# e-ink-display-v120.net
KiCad netlist of a schematic drawn in EAGLE
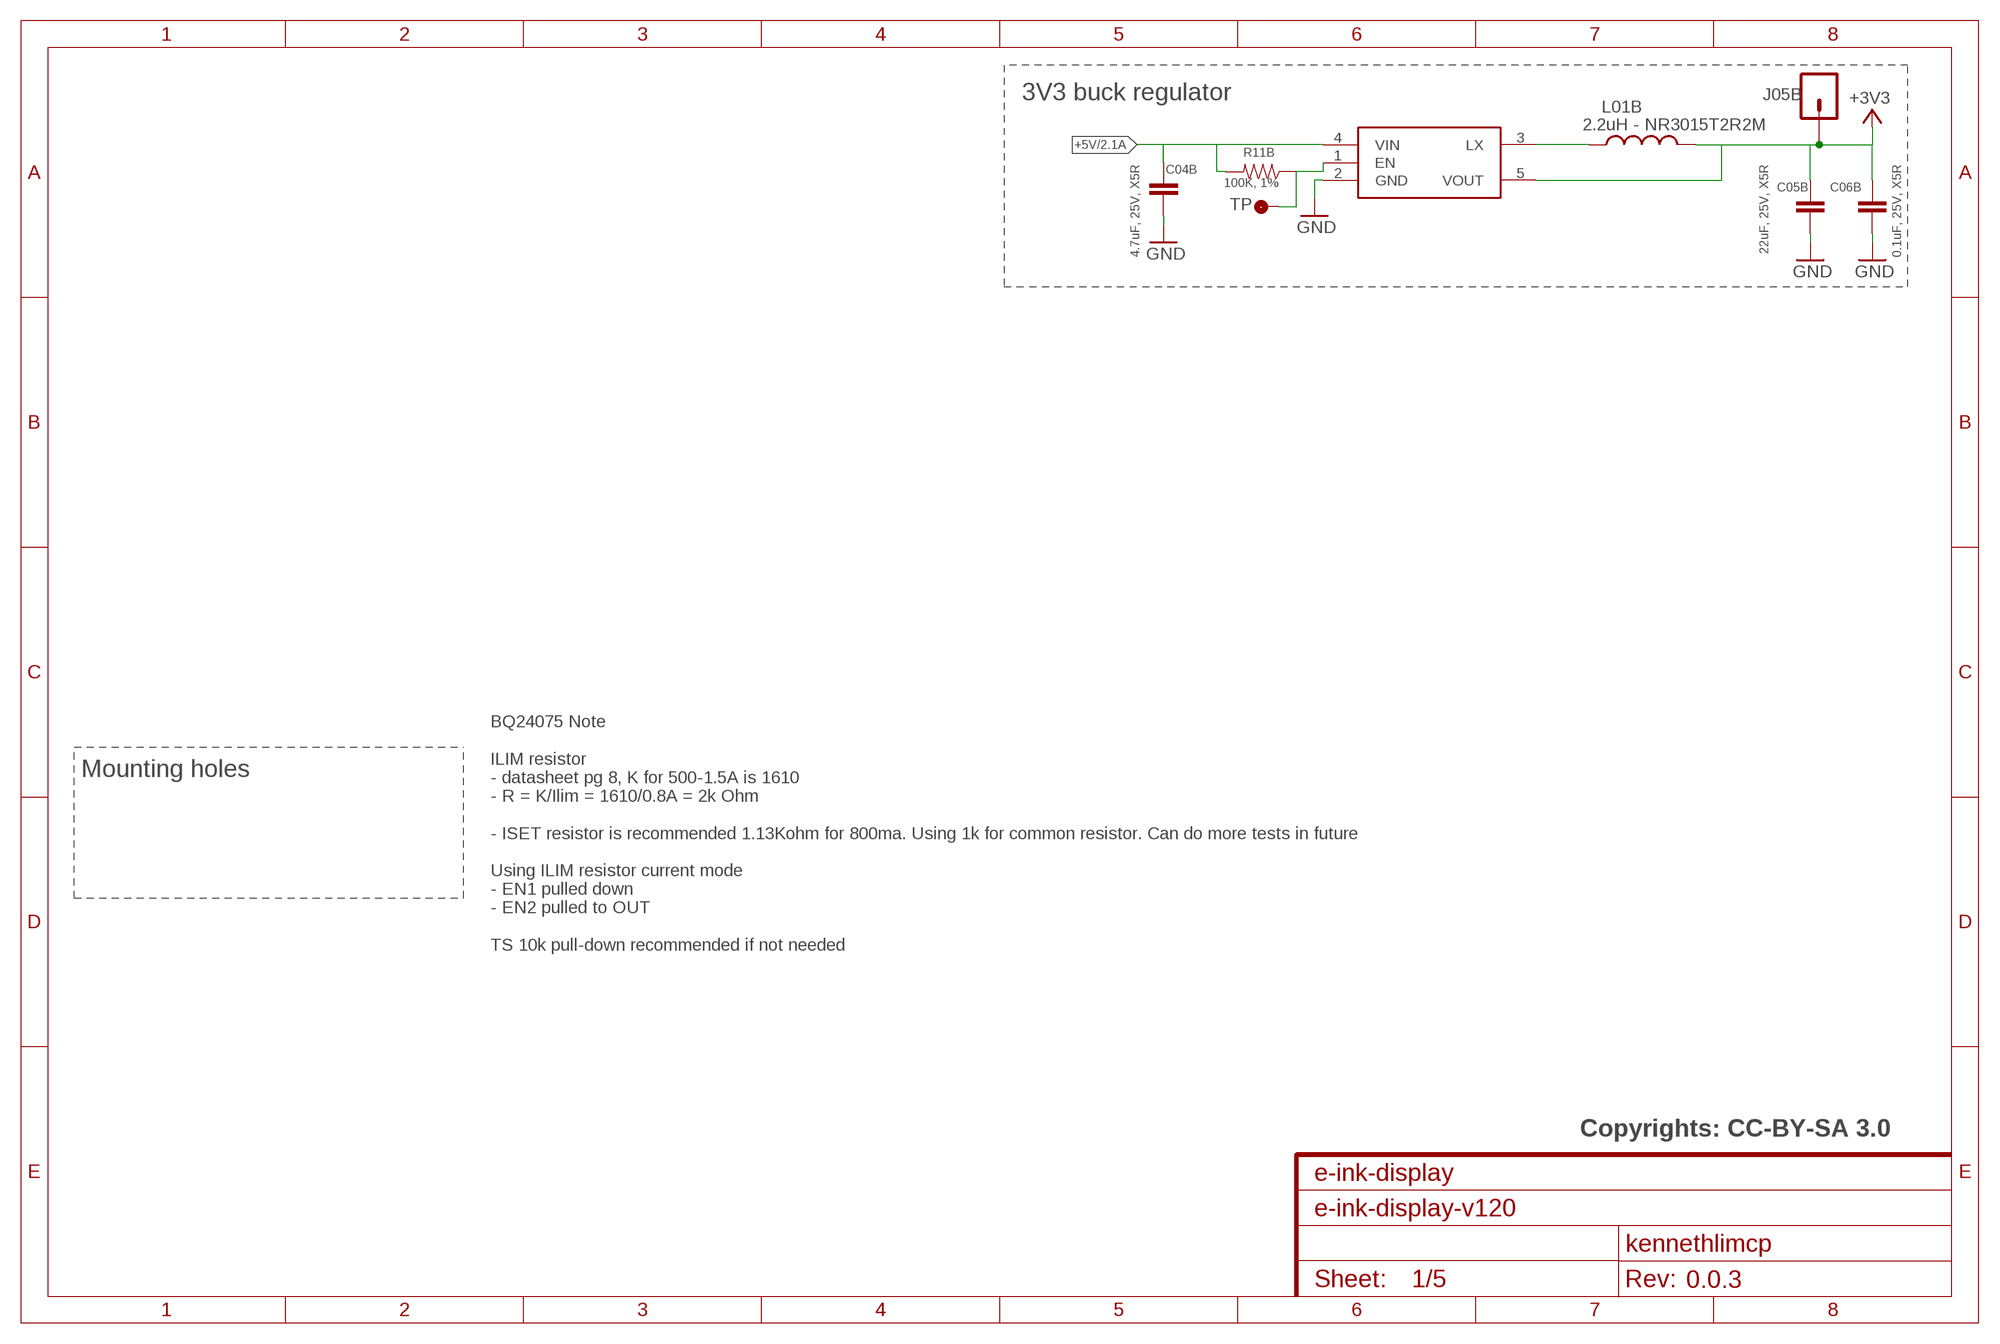
[diagram p0: schematic, sheet 1]
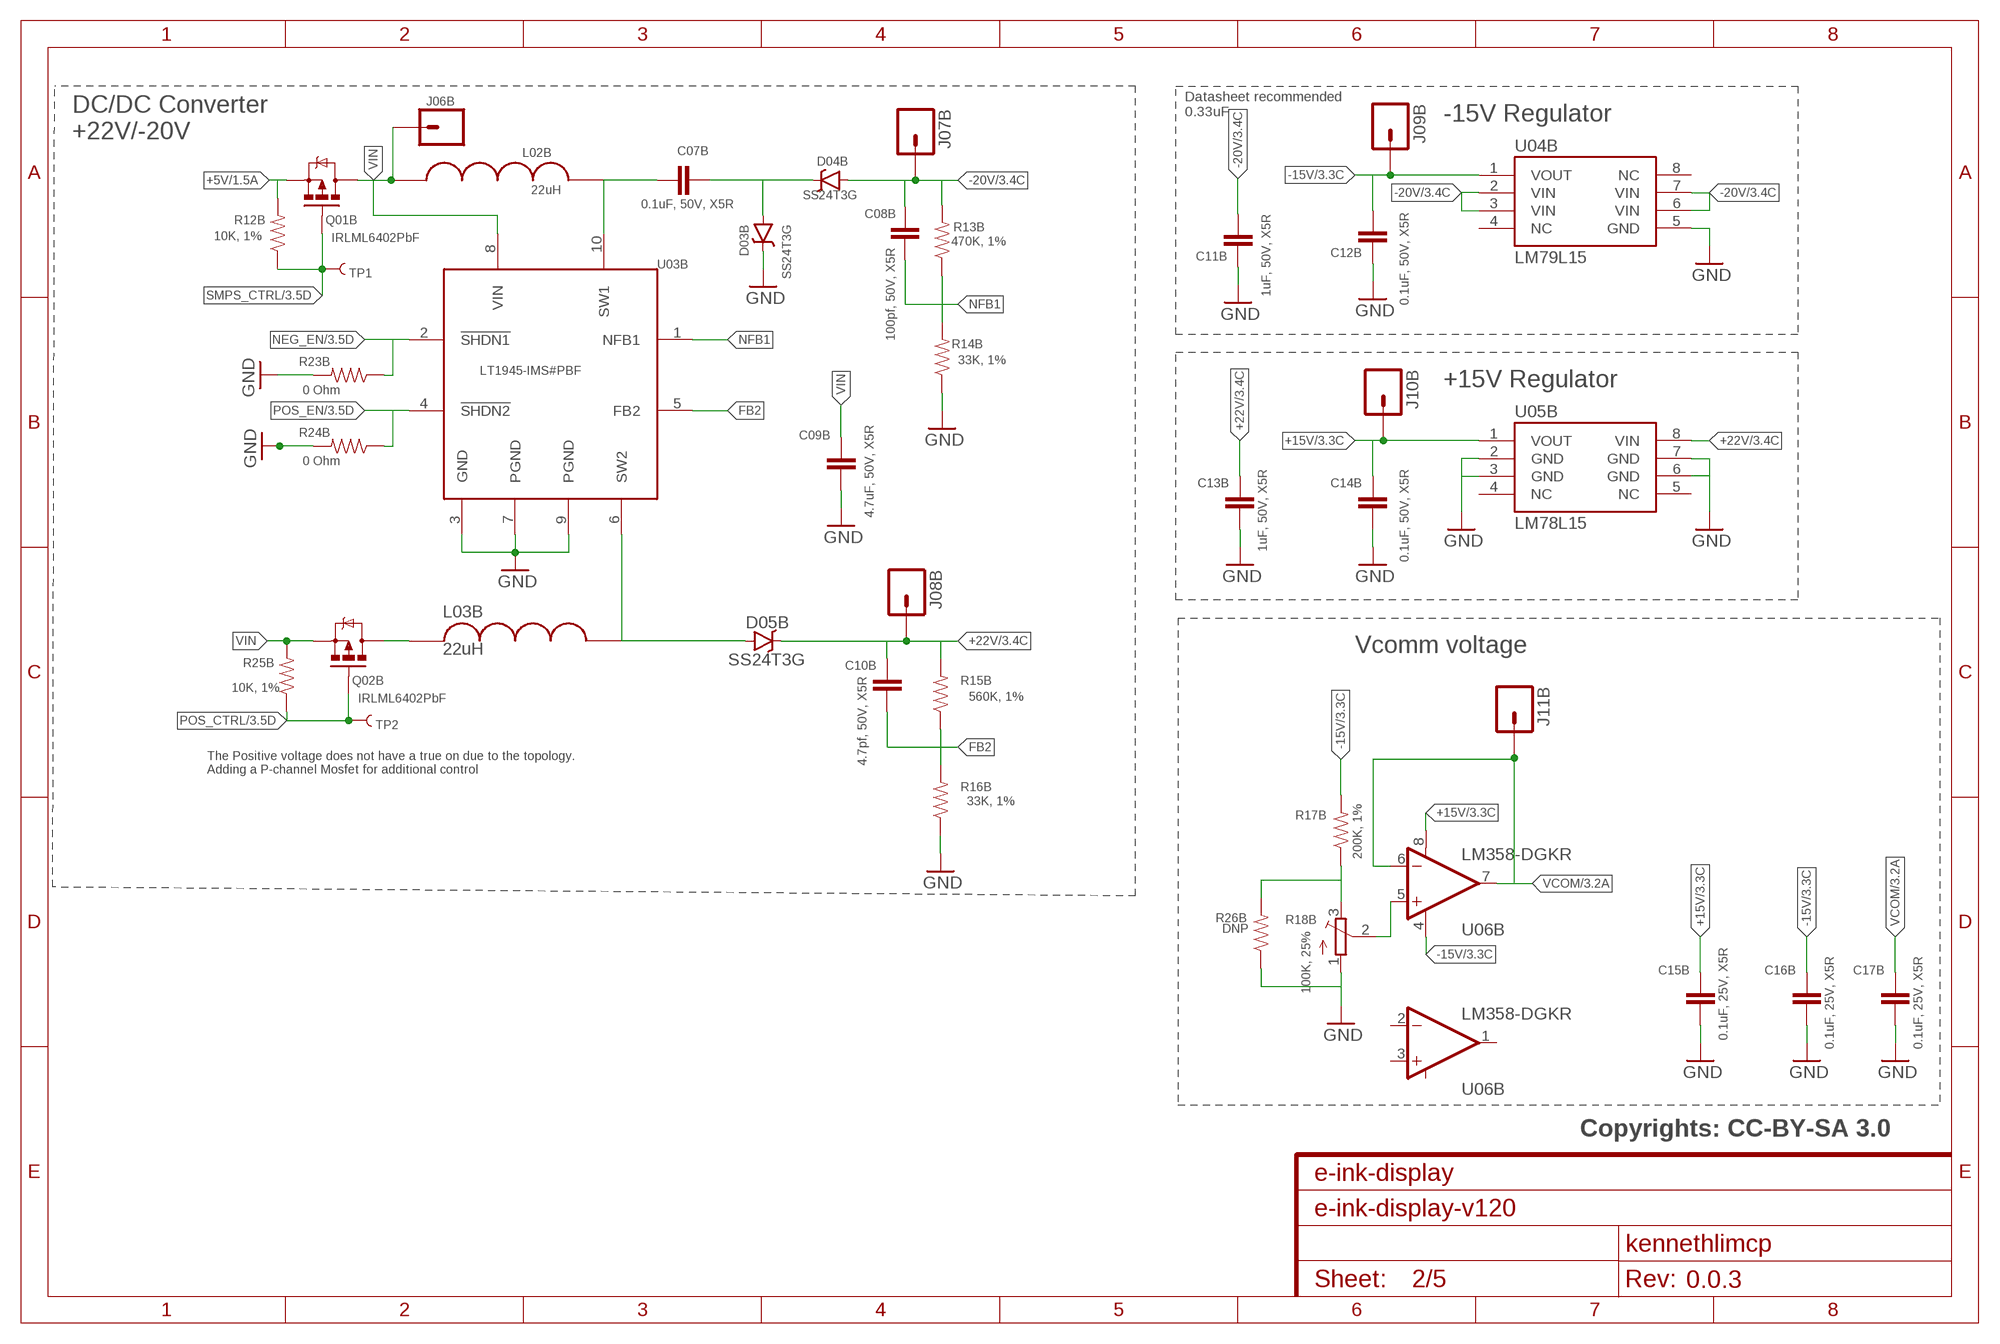
[diagram p1: schematic, sheet 2]
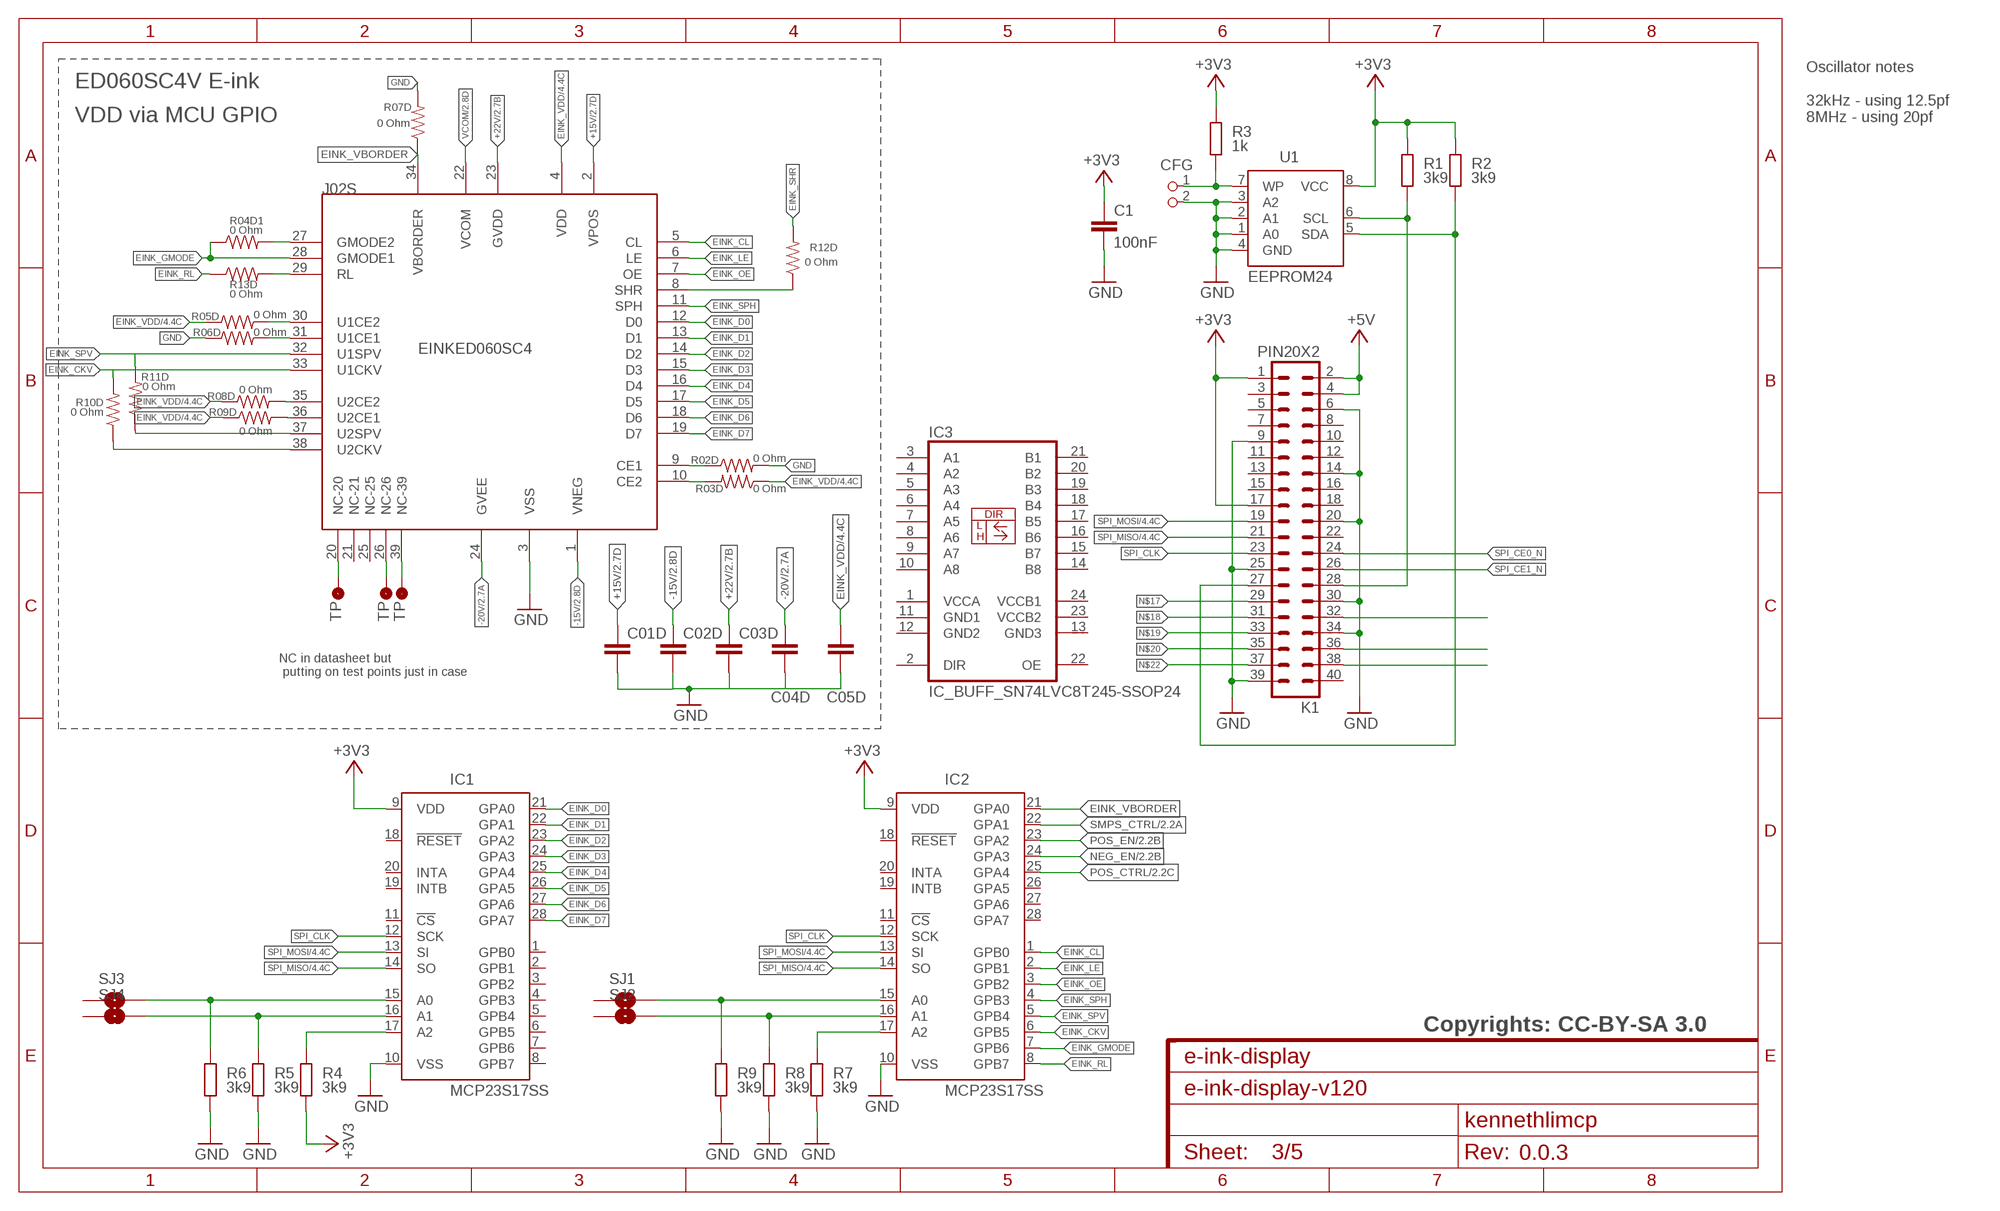
[diagram p2: schematic, sheet 3]
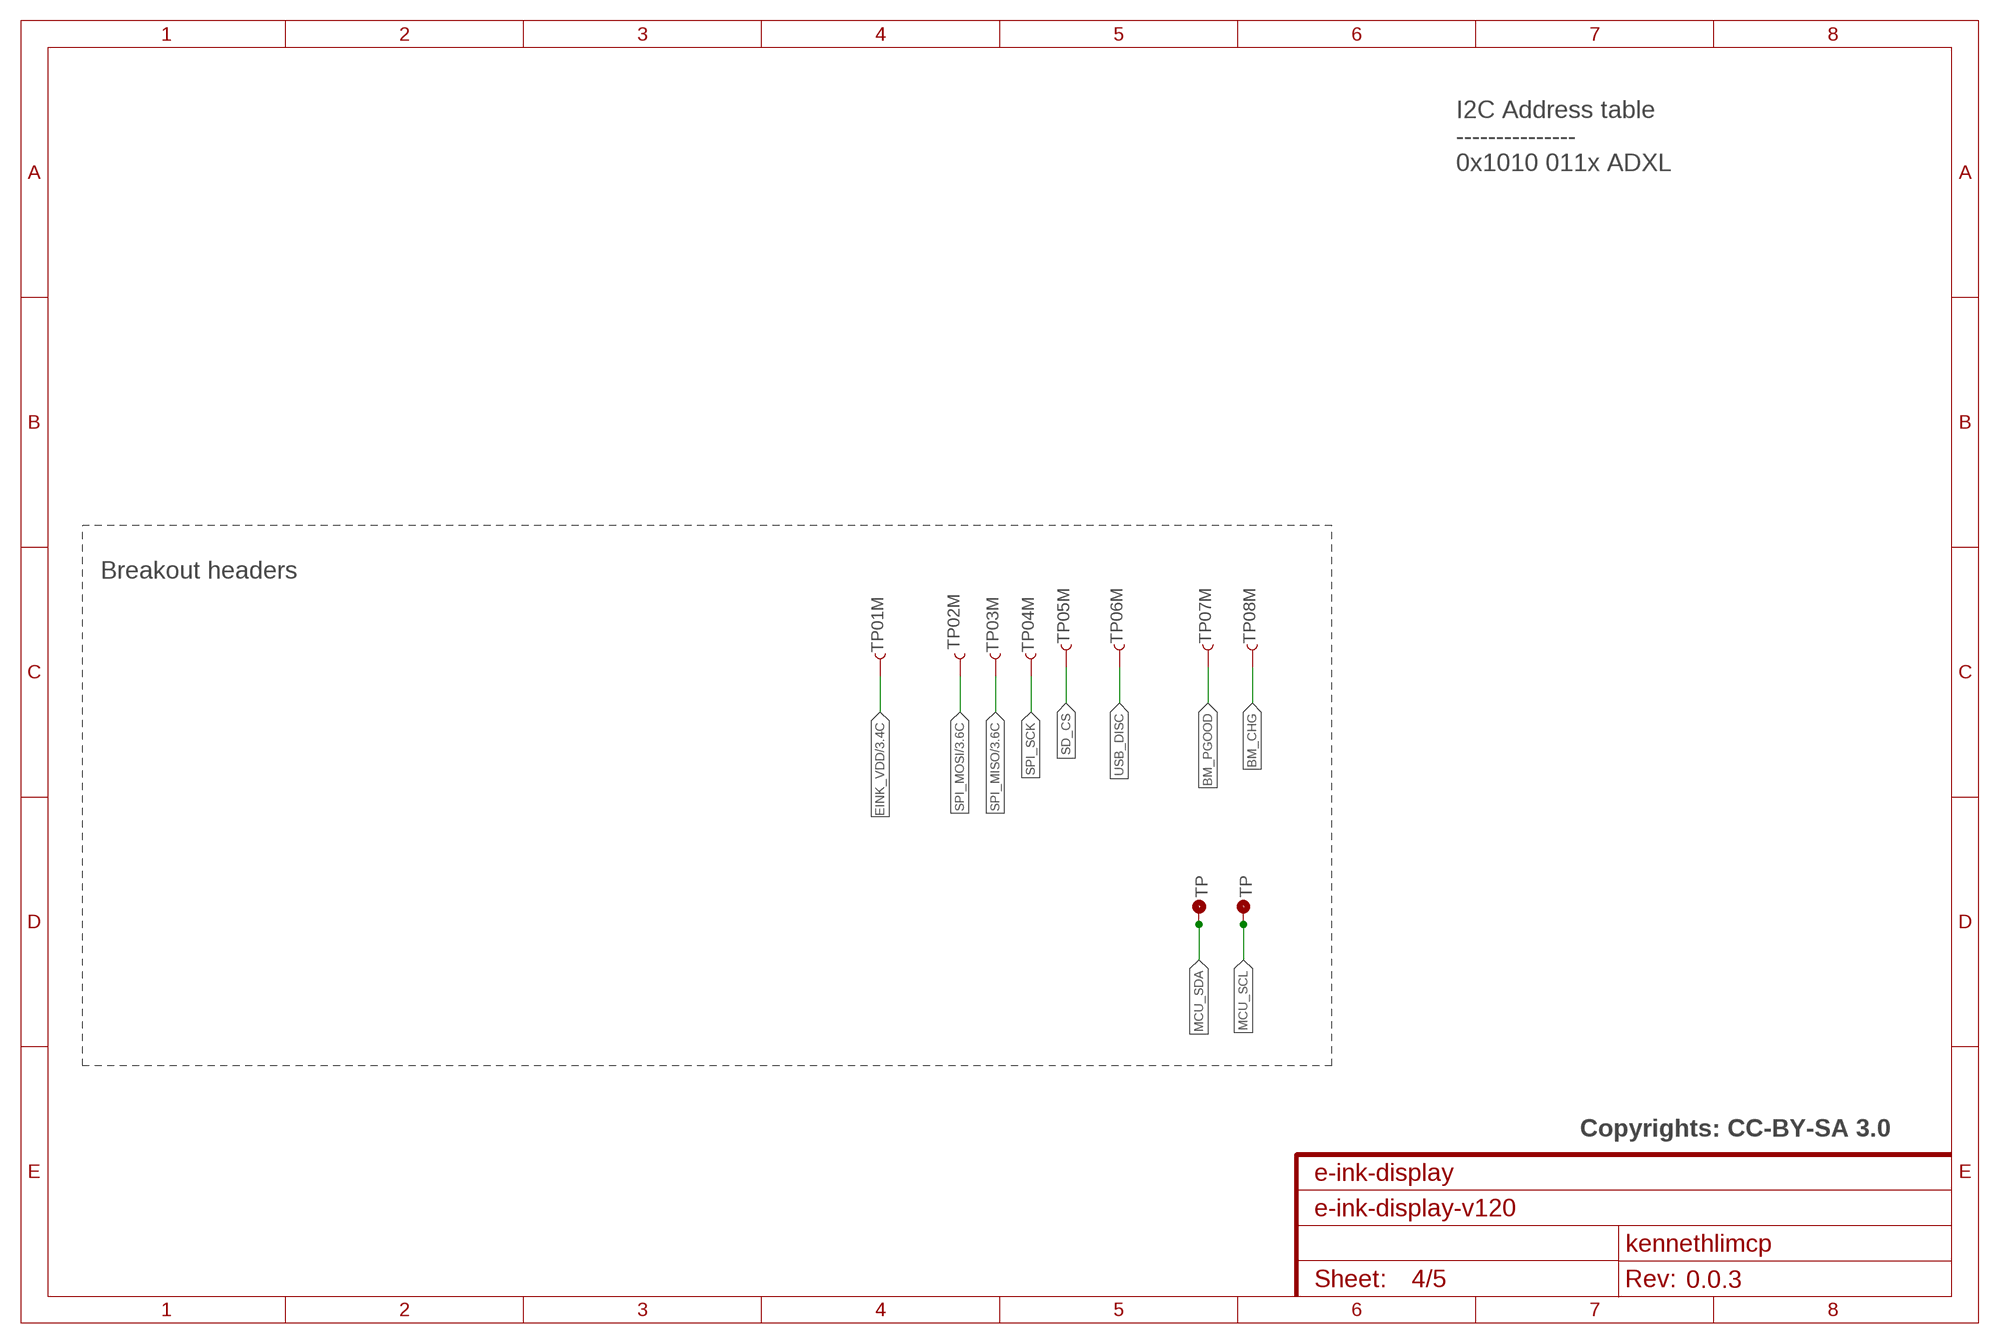
[diagram p3: schematic, sheet 4]
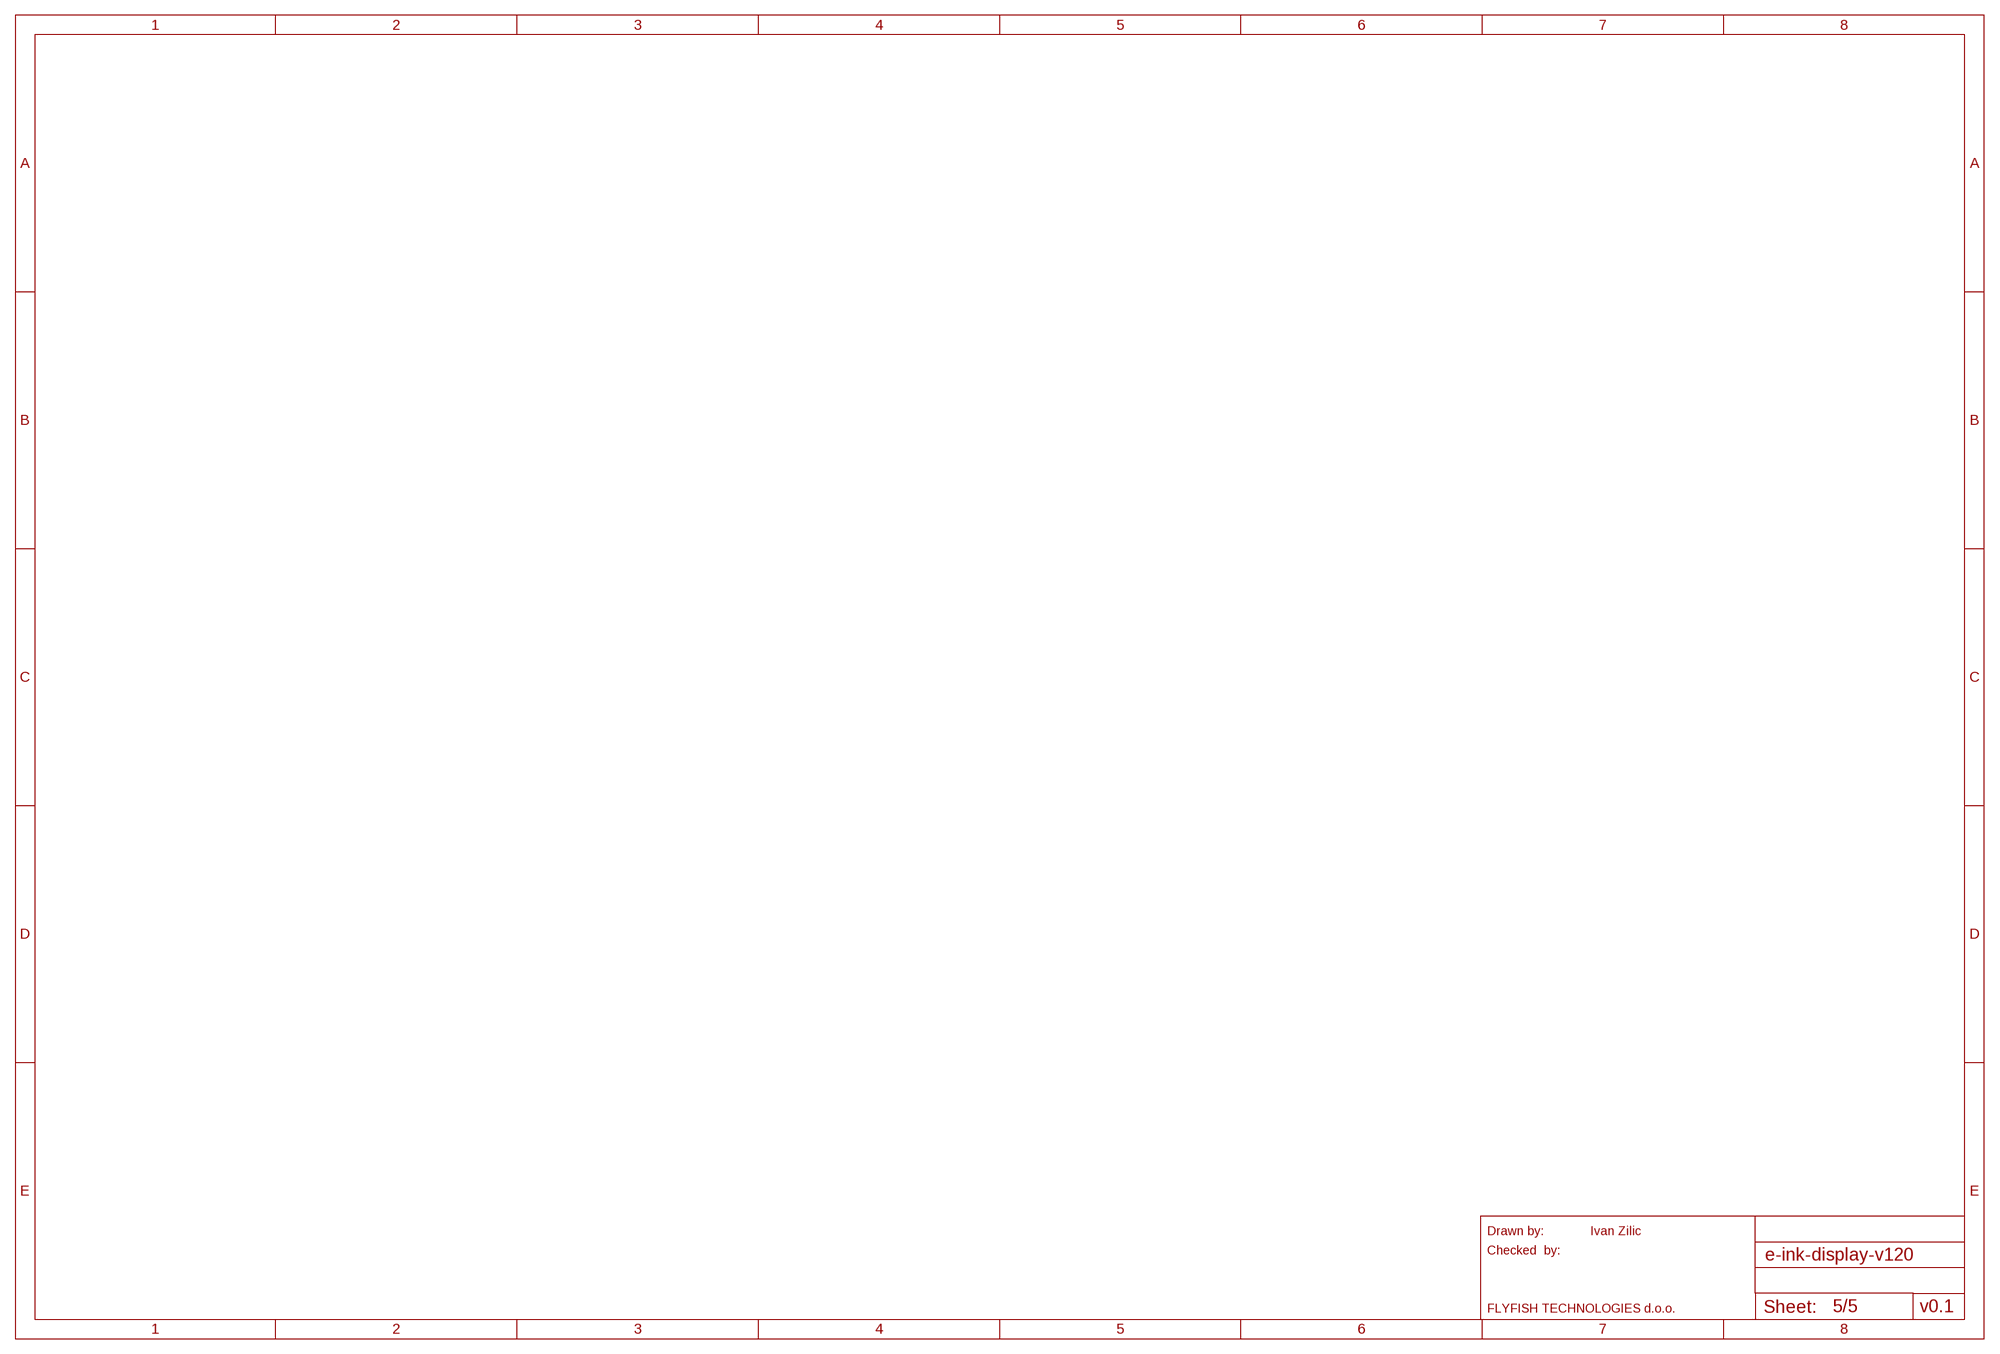
[diagram p4: schematic, sheet 5]

(export (version "E")
  (design (tool "Eeschema 10.0.6"))
  (components
    (comp (ref "TP01M")
      (value "TEST-POINTRD_THRU")
      (footprint "eagle-import:TP-RD_15TH")
      (libsource (lib "eagle-import") (part "TEST-POINTRD_THRU"))
    )
    (comp (ref "TP02M")
      (value "TEST-POINTRD_THRU")
      (footprint "eagle-import:TP-RD_15TH")
      (libsource (lib "eagle-import") (part "TEST-POINTRD_THRU"))
    )
    (comp (ref "TP03M")
      (value "TEST-POINTTP_15TH_THRU")
      (footprint "eagle-import:TP_15TH")
      (libsource (lib "eagle-import") (part "TEST-POINTTP_15TH_THRU"))
    )
    (comp (ref "TP04M")
      (value "TEST-POINTRD_THRU")
      (footprint "eagle-import:TP-RD_15TH")
      (libsource (lib "eagle-import") (part "TEST-POINTRD_THRU"))
    )
    (comp (ref "TP05M")
      (value "TEST-POINTRD_THRU")
      (footprint "eagle-import:TP-RD_15TH")
      (libsource (lib "eagle-import") (part "TEST-POINTRD_THRU"))
    )
    (comp (ref "TP06M")
      (value "TEST-POINTRD_THRU")
      (footprint "eagle-import:TP-RD_15TH")
      (libsource (lib "eagle-import") (part "TEST-POINTRD_THRU"))
    )
    (comp (ref "TP07M")
      (value "TEST-POINTRD_THRU")
      (footprint "eagle-import:TP-RD_15TH")
      (libsource (lib "eagle-import") (part "TEST-POINTRD_THRU"))
    )
    (comp (ref "TP08M")
      (value "TEST-POINTRD_THRU")
      (footprint "eagle-import:TP-RD_15TH")
      (libsource (lib "eagle-import") (part "TEST-POINTRD_THRU"))
    )
    (comp (ref "TP17M")
      (value "TP1")
      (footprint "eagle-import:TP35_BOT")
      (libsource (lib "eagle-import") (part "TP1"))
    )
    (comp (ref "TP18M")
      (value "TP1")
      (footprint "eagle-import:TP35_BOT")
      (libsource (lib "eagle-import") (part "TP1"))
    )
    (comp (ref "C04B")
      (value "4.7uF, 25V, X5R")
      (footprint "eagle-import:0603-CAP")
      (libsource (lib "eagle-import") (part "CAP0603-CAP"))
    )
    (comp (ref "C05B")
      (value "22uF, 25V, X5R")
      (footprint "eagle-import:0603-CAP")
      (libsource (lib "eagle-import") (part "CAP0603-CAP"))
    )
    (comp (ref "C06B")
      (value "0.1uF, 25V, X5R")
      (footprint "eagle-import:0603-CAP")
      (libsource (lib "eagle-import") (part "CAP0603-CAP"))
    )
    (comp (ref "J05B")
      (value "M01PTH")
      (footprint "eagle-import:1X01")
      (libsource (lib "eagle-import") (part "M01PTH"))
    )
    (comp (ref "L01B")
      (value "2.2uH - NR3015T2R2M")
      (footprint "eagle-import:INDUCTOR-NR3015")
      (libsource (lib "eagle-import") (part "INDUCTOR-SPARKFUNNR3015T4R7M"))
    )
    (comp (ref "R11B")
      (value "100K, 1%")
      (footprint "eagle-import:0603-RES")
      (libsource (lib "eagle-import") (part "RESISTOR0603-RES"))
    )
    (comp (ref "TP01B")
      (value "TP1")
      (footprint "eagle-import:TP35_BOT")
      (libsource (lib "eagle-import") (part "TP1"))
    )
    (comp (ref "U02B")
      (value "R8008-33")
      (footprint "eagle-import:SOT23-5")
      (libsource (lib "eagle-import") (part "R8008-33"))
    )
    (comp (ref "C1")
      (value "100nF")
      (footprint "eagle-import:C0805K")
      (libsource (lib "eagle-import") (part "C-EUC0805K"))
    )
    (comp (ref "C01D")
      (value "100nF")
      (footprint "eagle-import:0603-CAP")
      (libsource (lib "eagle-import") (part "CAP0603-CAP"))
    )
    (comp (ref "C02D")
      (value "100nF")
      (footprint "eagle-import:0603-CAP")
      (libsource (lib "eagle-import") (part "CAP0603-CAP"))
    )
    (comp (ref "C03D")
      (value "100nF")
      (footprint "eagle-import:0603-CAP")
      (libsource (lib "eagle-import") (part "CAP0603-CAP"))
    )
    (comp (ref "C04D")
      (value "100nF")
      (footprint "eagle-import:0603-CAP")
      (libsource (lib "eagle-import") (part "CAP0603-CAP"))
    )
    (comp (ref "C05D")
      (value "100nF")
      (footprint "eagle-import:0603-CAP")
      (libsource (lib "eagle-import") (part "CAP0603-CAP"))
    )
    (comp (ref "CFG")
      (value "PIN2_100")
      (footprint "eagle-import:PIN_W_2")
      (libsource (lib "eagle-import") (part "PIN2_100"))
    )
    (comp (ref "IC1")
      (value "MCP23S17SS")
      (footprint "eagle-import:SSOP28")
      (fields (field (name "MF") "MICROCHIP") (field (name "MPN") "MCP23S17-E/SS"))
      (libsource (lib "eagle-import") (part "MCP23S17SS"))
    )
    (comp (ref "IC2")
      (value "MCP23S17SS")
      (footprint "eagle-import:SSOP28")
      (fields (field (name "MF") "MICROCHIP") (field (name "MPN") "MCP23S17-E/SS"))
      (libsource (lib "eagle-import") (part "MCP23S17SS"))
    )
    (comp (ref "IC3")
      (value "IC_BUFF_SN74LVC8T245-SSOP24")
      (footprint "eagle-import:SSOP24")
      (libsource (lib "eagle-import") (part "IC_BUFF_SN74LVC8T245-SSOP24"))
    )
    (comp (ref "J02S")
      (value "EINKED060SC4")
      (footprint "eagle-import:FPC-0.3-39")
      (libsource (lib "eagle-import") (part "EINKED060SC4"))
    )
    (comp (ref "K1")
      (value "PIN20X2")
      (footprint "eagle-import:PIN_20X2")
      (libsource (lib "eagle-import") (part "PIN20X2"))
    )
    (comp (ref "R1")
      (value "3k9")
      (footprint "eagle-import:M0805")
      (fields (field (name "TOLERANCE") "5%"))
      (libsource (lib "eagle-import") (part "R-EU_M0805"))
    )
    (comp (ref "R2")
      (value "3k9")
      (footprint "eagle-import:M0805")
      (fields (field (name "TOLERANCE") "5%"))
      (libsource (lib "eagle-import") (part "R-EU_M0805"))
    )
    (comp (ref "R02D")
      (value "0 Ohm")
      (footprint "eagle-import:0603-RES")
      (libsource (lib "eagle-import") (part "RESISTOR0603-RES"))
    )
    (comp (ref "R3")
      (value "1k")
      (footprint "eagle-import:M0805")
      (fields (field (name "TOLERANCE") "5%"))
      (libsource (lib "eagle-import") (part "R-EU_M0805"))
    )
    (comp (ref "R03D")
      (value "0 Ohm")
      (footprint "eagle-import:0603-RES")
      (libsource (lib "eagle-import") (part "RESISTOR0603-RES"))
    )
    (comp (ref "R4")
      (value "3k9")
      (footprint "eagle-import:M0805")
      (fields (field (name "TOLERANCE") "5%"))
      (libsource (lib "eagle-import") (part "R-EU_M0805"))
    )
    (comp (ref "R04D1")
      (value "0 Ohm")
      (footprint "eagle-import:0603-RES")
      (libsource (lib "eagle-import") (part "RESISTOR0603-RES"))
    )
    (comp (ref "R5")
      (value "3k9")
      (footprint "eagle-import:M0805")
      (fields (field (name "TOLERANCE") "5%"))
      (libsource (lib "eagle-import") (part "R-EU_M0805"))
    )
    (comp (ref "R05D")
      (value "0 Ohm")
      (footprint "eagle-import:0603-RES")
      (libsource (lib "eagle-import") (part "RESISTOR0603-RES"))
    )
    (comp (ref "R6")
      (value "3k9")
      (footprint "eagle-import:M0805")
      (fields (field (name "TOLERANCE") "5%"))
      (libsource (lib "eagle-import") (part "R-EU_M0805"))
    )
    (comp (ref "R06D")
      (value "0 Ohm")
      (footprint "eagle-import:0603-RES")
      (libsource (lib "eagle-import") (part "RESISTOR0603-RES"))
    )
    (comp (ref "R7")
      (value "3k9")
      (footprint "eagle-import:M0805")
      (fields (field (name "TOLERANCE") "5%"))
      (libsource (lib "eagle-import") (part "R-EU_M0805"))
    )
    (comp (ref "R07D")
      (value "0 Ohm")
      (footprint "eagle-import:0603-RES")
      (libsource (lib "eagle-import") (part "RESISTOR0603-RES"))
    )
    (comp (ref "R8")
      (value "3k9")
      (footprint "eagle-import:M0805")
      (fields (field (name "TOLERANCE") "5%"))
      (libsource (lib "eagle-import") (part "R-EU_M0805"))
    )
    (comp (ref "R08D")
      (value "0 Ohm")
      (footprint "eagle-import:0603-RES")
      (libsource (lib "eagle-import") (part "RESISTOR0603-RES"))
    )
    (comp (ref "R9")
      (value "3k9")
      (footprint "eagle-import:M0805")
      (fields (field (name "TOLERANCE") "5%"))
      (libsource (lib "eagle-import") (part "R-EU_M0805"))
    )
    (comp (ref "R09D")
      (value "0 Ohm")
      (footprint "eagle-import:0603-RES")
      (libsource (lib "eagle-import") (part "RESISTOR0603-RES"))
    )
    (comp (ref "R10D")
      (value "0 Ohm")
      (footprint "eagle-import:0603-RES")
      (libsource (lib "eagle-import") (part "RESISTOR0603-RES"))
    )
    (comp (ref "R11D")
      (value "0 Ohm")
      (footprint "eagle-import:0603-RES")
      (libsource (lib "eagle-import") (part "RESISTOR0603-RES"))
    )
    (comp (ref "R12D")
      (value "0 Ohm")
      (footprint "eagle-import:0603-RES")
      (libsource (lib "eagle-import") (part "RESISTOR0603-RES"))
    )
    (comp (ref "R13D")
      (value "0 Ohm")
      (footprint "eagle-import:0603-RES")
      (libsource (lib "eagle-import") (part "RESISTOR0603-RES"))
    )
    (comp (ref "SJ1")
      (value "SOLDERJUMPERNO")
      (footprint "eagle-import:SJ_2S-NO")
      (libsource (lib "eagle-import") (part "SOLDERJUMPERNO"))
    )
    (comp (ref "SJ2")
      (value "SOLDERJUMPERNO")
      (footprint "eagle-import:SJ_2S-NO")
      (libsource (lib "eagle-import") (part "SOLDERJUMPERNO"))
    )
    (comp (ref "SJ3")
      (value "SOLDERJUMPERNO")
      (footprint "eagle-import:SJ_2S-NO")
      (libsource (lib "eagle-import") (part "SOLDERJUMPERNO"))
    )
    (comp (ref "SJ4")
      (value "SOLDERJUMPERNO")
      (footprint "eagle-import:SJ_2S-NO")
      (libsource (lib "eagle-import") (part "SOLDERJUMPERNO"))
    )
    (comp (ref "U$1")
      (value "TP1")
      (footprint "eagle-import:TP35_BOT")
      (libsource (lib "eagle-import") (part "TP1"))
    )
    (comp (ref "U$8")
      (value "TP1")
      (footprint "eagle-import:TP35_BOT")
      (libsource (lib "eagle-import") (part "TP1"))
    )
    (comp (ref "U$9")
      (value "TP1")
      (footprint "eagle-import:TP35_BOT")
      (libsource (lib "eagle-import") (part "TP1"))
    )
    (comp (ref "U1")
      (value "EEPROM24")
      (footprint "eagle-import:SOIC8")
      (libsource (lib "eagle-import") (part "EEPROM24"))
    )
    (comp (ref "C07B")
      (value "0.1uF, 50V, X5R")
      (footprint "eagle-import:0603-CAP")
      (libsource (lib "eagle-import") (part "CAP0603-CAP"))
    )
    (comp (ref "C08B")
      (value "100pf, 50V, X5R")
      (footprint "eagle-import:0603-CAP")
      (libsource (lib "eagle-import") (part "CAP0603-CAP"))
    )
    (comp (ref "C09B")
      (value "4.7uF, 50V, X5R")
      (footprint "eagle-import:0603-CAP")
      (libsource (lib "eagle-import") (part "CAP0603-CAP"))
    )
    (comp (ref "C10B")
      (value "4.7pf, 50V, X5R")
      (footprint "eagle-import:0603-CAP")
      (libsource (lib "eagle-import") (part "CAP0603-CAP"))
    )
    (comp (ref "C11B")
      (value "1uF, 50V, X5R")
      (footprint "eagle-import:0603-CAP")
      (libsource (lib "eagle-import") (part "CAP0603-CAP"))
    )
    (comp (ref "C12B")
      (value "0.1uF, 50V, X5R")
      (footprint "eagle-import:0603-CAP")
      (libsource (lib "eagle-import") (part "CAP0603-CAP"))
    )
    (comp (ref "C13B")
      (value "1uF, 50V, X5R")
      (footprint "eagle-import:0603-CAP")
      (libsource (lib "eagle-import") (part "CAP0603-CAP"))
    )
    (comp (ref "C14B")
      (value "0.1uF, 50V, X5R")
      (footprint "eagle-import:0603-CAP")
      (libsource (lib "eagle-import") (part "CAP0603-CAP"))
    )
    (comp (ref "C15B")
      (value "0.1uF, 25V, X5R")
      (footprint "eagle-import:0603-CAP")
      (libsource (lib "eagle-import") (part "CAP0603-CAP"))
    )
    (comp (ref "C16B")
      (value "0.1uF, 25V, X5R")
      (footprint "eagle-import:0603-CAP")
      (libsource (lib "eagle-import") (part "CAP0603-CAP"))
    )
    (comp (ref "C17B")
      (value "0.1uF, 25V, X5R")
      (footprint "eagle-import:0603-CAP")
      (libsource (lib "eagle-import") (part "CAP0603-CAP"))
    )
    (comp (ref "D03B")
      (value "SS24T3G")
      (footprint "eagle-import:SMA-DIODE")
      (libsource (lib "eagle-import") (part "DIODE-SCHOTTKY-SS24T3G"))
    )
    (comp (ref "D04B")
      (value "SS24T3G")
      (footprint "eagle-import:SMA-DIODE")
      (libsource (lib "eagle-import") (part "DIODE-SCHOTTKY-SS24T3G"))
    )
    (comp (ref "D05B")
      (value "SS24T3G")
      (footprint "eagle-import:SMA-DIODE")
      (libsource (lib "eagle-import") (part "DIODE-SCHOTTKY-SS24T3G"))
    )
    (comp (ref "J06B")
      (value "M01PTH")
      (footprint "eagle-import:1X01")
      (libsource (lib "eagle-import") (part "M01PTH"))
    )
    (comp (ref "J07B")
      (value "M01PTH")
      (footprint "eagle-import:1X01")
      (libsource (lib "eagle-import") (part "M01PTH"))
    )
    (comp (ref "J08B")
      (value "M01PTH")
      (footprint "eagle-import:1X01")
      (libsource (lib "eagle-import") (part "M01PTH"))
    )
    (comp (ref "J09B")
      (value "M01PTH")
      (footprint "eagle-import:1X01")
      (libsource (lib "eagle-import") (part "M01PTH"))
    )
    (comp (ref "J10B")
      (value "M01PTH")
      (footprint "eagle-import:1X01")
      (libsource (lib "eagle-import") (part "M01PTH"))
    )
    (comp (ref "J11B")
      (value "M01PTH")
      (footprint "eagle-import:1X01")
      (libsource (lib "eagle-import") (part "M01PTH"))
    )
    (comp (ref "L02B")
      (value "22uH")
      (footprint "eagle-import:4040(1515)")
      (libsource (lib "eagle-import") (part "03-INDUCTOR"))
    )
    (comp (ref "L03B")
      (value "22uH")
      (footprint "eagle-import:4040(1515)")
      (libsource (lib "eagle-import") (part "03-INDUCTOR"))
    )
    (comp (ref "Q01B")
      (value "IRLML6402PbF")
      (footprint "eagle-import:SOT23-3")
      (libsource (lib "eagle-import") (part "MOSFET-PCHANNELSMD"))
    )
    (comp (ref "Q02B")
      (value "IRLML6402PbF")
      (footprint "eagle-import:SOT23-3")
      (libsource (lib "eagle-import") (part "MOSFET-PCHANNELSMD"))
    )
    (comp (ref "R12B")
      (value "10K, 1%")
      (footprint "eagle-import:0603-RES")
      (libsource (lib "eagle-import") (part "RESISTOR0603-RES"))
    )
    (comp (ref "R13B")
      (value "470K, 1%")
      (footprint "eagle-import:0603-RES")
      (libsource (lib "eagle-import") (part "RESISTOR0603-RES"))
    )
    (comp (ref "R14B")
      (value "33K, 1%")
      (footprint "eagle-import:0603-RES")
      (libsource (lib "eagle-import") (part "RESISTOR0603-RES"))
    )
    (comp (ref "R15B")
      (value "560K, 1%")
      (footprint "eagle-import:0603-RES")
      (libsource (lib "eagle-import") (part "RESISTOR0603-RES"))
    )
    (comp (ref "R16B")
      (value "33K, 1%")
      (footprint "eagle-import:0603-RES")
      (libsource (lib "eagle-import") (part "RESISTOR0603-RES"))
    )
    (comp (ref "R17B")
      (value "200K, 1%")
      (footprint "eagle-import:0603-RES")
      (libsource (lib "eagle-import") (part "RESISTOR0603-RES"))
    )
    (comp (ref "R18B")
      (value "100K, 25%")
      (footprint "eagle-import:TC33X")
      (libsource (lib "eagle-import") (part "TRIMPOTTC33X"))
    )
    (comp (ref "R23B")
      (value "0 Ohm")
      (footprint "eagle-import:0603-RES")
      (libsource (lib "eagle-import") (part "RESISTOR0603-RES"))
    )
    (comp (ref "R24B")
      (value "0 Ohm")
      (footprint "eagle-import:0603-RES")
      (libsource (lib "eagle-import") (part "RESISTOR0603-RES"))
    )
    (comp (ref "R25B")
      (value "10K, 1%")
      (footprint "eagle-import:0603-RES")
      (libsource (lib "eagle-import") (part "RESISTOR0603-RES"))
    )
    (comp (ref "R26B")
      (value "DNP")
      (footprint "eagle-import:0603-RES")
      (libsource (lib "eagle-import") (part "RESISTOR0603-RES"))
    )
    (comp (ref "TP1")
      (value "TEST-POINTRD_THRU")
      (footprint "eagle-import:TP-RD_15TH")
      (libsource (lib "eagle-import") (part "TEST-POINTRD_THRU"))
    )
    (comp (ref "TP2")
      (value "TEST-POINTRD_THRU")
      (footprint "eagle-import:TP-RD_15TH")
      (libsource (lib "eagle-import") (part "TEST-POINTRD_THRU"))
    )
    (comp (ref "U03B")
      (value "LT1945-IMS#PBF")
      (footprint "eagle-import:MSOP-10")
      (libsource (lib "eagle-import") (part "LT1945-IMS#PBF"))
    )
    (comp (ref "U04B")
      (value "LM79L15")
      (footprint "eagle-import:SO08")
      (libsource (lib "eagle-import") (part "LM79L15"))
    )
    (comp (ref "U05B")
      (value "LM78L15")
      (footprint "eagle-import:SO08")
      (libsource (lib "eagle-import") (part "LM78L15"))
    )
    (comp (ref "U06B")
      (value "LM358-DGKR")
      (footprint "eagle-import:MSOP-8")
      (libsource (lib "eagle-import") (part "LM358-DGKR"))
    )
  )
  (nets
    (net (code "1") (name "+3V3") (class "Default")
      (node (ref "C05B") (pin "2") (pinfunction "2_2") (pintype "passive"))
      (node (ref "C06B") (pin "2") (pinfunction "2_2") (pintype "passive"))
      (node (ref "C1") (pin "1") (pinfunction "1_1") (pintype "passive"))
      (node (ref "IC1") (pin "9") (pinfunction "VDD_9") (pintype "power_in"))
      (node (ref "IC2") (pin "9") (pinfunction "VDD_9") (pintype "power_in"))
      (node (ref "J05B") (pin "1") (pinfunction "1_1") (pintype "passive"))
      (node (ref "K1") (pin "1") (pinfunction "1_1") (pintype "passive"))
      (node (ref "K1") (pin "17") (pinfunction "17_17") (pintype "passive"))
      (node (ref "L01B") (pin "2") (pinfunction "2_2") (pintype "passive"))
      (node (ref "R1") (pin "2") (pinfunction "2_2") (pintype "passive"))
      (node (ref "R2") (pin "2") (pinfunction "2_2") (pintype "passive"))
      (node (ref "R3") (pin "2") (pinfunction "2_2") (pintype "passive"))
      (node (ref "R4") (pin "1") (pinfunction "1_1") (pintype "passive"))
      (node (ref "U02B") (pin "5") (pinfunction "VOUT_5") (pintype "bidirectional"))
      (node (ref "U1") (pin "8") (pinfunction "VCC_8") (pintype "power_in"))
    )
    (net (code "2") (name "+5V") (class "Default")
      (node (ref "C04B") (pin "2") (pinfunction "2_2") (pintype "passive"))
      (node (ref "K1") (pin "2") (pinfunction "2_2") (pintype "passive"))
      (node (ref "K1") (pin "4") (pinfunction "4_4") (pintype "passive"))
      (node (ref "Q01B") (pin "2") (pinfunction "S_2") (pintype "passive"))
      (node (ref "R11B") (pin "2") (pinfunction "2_2") (pintype "passive"))
      (node (ref "R12B") (pin "2") (pinfunction "2_2") (pintype "passive"))
      (node (ref "U02B") (pin "4") (pinfunction "VIN_4") (pintype "bidirectional"))
    )
    (net (code "3") (name "+15V") (class "Default")
      (node (ref "C01D") (pin "1") (pinfunction "1_1") (pintype "passive"))
      (node (ref "C14B") (pin "2") (pinfunction "2_2") (pintype "passive"))
      (node (ref "C15B") (pin "2") (pinfunction "2_2") (pintype "passive"))
      (node (ref "J02S") (pin "2") (pinfunction "VPOS_2") (pintype "bidirectional"))
      (node (ref "J10B") (pin "1") (pinfunction "1_1") (pintype "passive"))
      (node (ref "U05B") (pin "1") (pinfunction "VOUT_1") (pintype "bidirectional"))
      (node (ref "U06B") (pin "8") (pinfunction "V+_8") (pintype "power_in"))
    )
    (net (code "4") (name "+22V") (class "Default")
      (node (ref "C03D") (pin "1") (pinfunction "1_1") (pintype "passive"))
      (node (ref "C10B") (pin "2") (pinfunction "2_2") (pintype "passive"))
      (node (ref "C13B") (pin "2") (pinfunction "2_2") (pintype "passive"))
      (node (ref "D05B") (pin "C") (pinfunction "C_C") (pintype "passive"))
      (node (ref "J02S") (pin "23") (pinfunction "GVDD_23") (pintype "bidirectional"))
      (node (ref "J08B") (pin "1") (pinfunction "1_1") (pintype "passive"))
      (node (ref "R15B") (pin "2") (pinfunction "2_2") (pintype "passive"))
      (node (ref "U05B") (pin "8") (pinfunction "VIN_8") (pintype "bidirectional"))
    )
    (net (code "5") (name "-15V") (class "Default")
      (node (ref "C02D") (pin "1") (pinfunction "1_1") (pintype "passive"))
      (node (ref "C12B") (pin "2") (pinfunction "2_2") (pintype "passive"))
      (node (ref "C16B") (pin "2") (pinfunction "2_2") (pintype "passive"))
      (node (ref "J02S") (pin "1") (pinfunction "VNEG_1") (pintype "bidirectional"))
      (node (ref "J09B") (pin "1") (pinfunction "1_1") (pintype "passive"))
      (node (ref "R17B") (pin "2") (pinfunction "2_2") (pintype "passive"))
      (node (ref "U04B") (pin "1") (pinfunction "VOUT_1") (pintype "bidirectional"))
      (node (ref "U06B") (pin "4") (pinfunction "V-_4") (pintype "power_in"))
    )
    (net (code "6") (name "-20V") (class "Default")
      (node (ref "C04D") (pin "1") (pinfunction "1_1") (pintype "passive"))
      (node (ref "C08B") (pin "2") (pinfunction "2_2") (pintype "passive"))
      (node (ref "C11B") (pin "2") (pinfunction "2_2") (pintype "passive"))
      (node (ref "D04B") (pin "A") (pinfunction "A_A") (pintype "passive"))
      (node (ref "J02S") (pin "24") (pinfunction "GVEE_24") (pintype "bidirectional"))
      (node (ref "J07B") (pin "1") (pinfunction "1_1") (pintype "passive"))
      (node (ref "R13B") (pin "2") (pinfunction "2_2") (pintype "passive"))
      (node (ref "U04B") (pin "2") (pinfunction "VIN_2") (pintype "bidirectional"))
      (node (ref "U04B") (pin "3") (pinfunction "VIN_3") (pintype "bidirectional"))
      (node (ref "U04B") (pin "6") (pinfunction "VIN_6") (pintype "bidirectional"))
      (node (ref "U04B") (pin "7") (pinfunction "VIN_7") (pintype "bidirectional"))
    )
    (net (code "7") (name "BM_CHG") (class "Default")
      (node (ref "TP08M") (pin "P$1") (pinfunction "1_P$1") (pintype "bidirectional"))
    )
    (net (code "8") (name "BM_PGOOD") (class "Default")
      (node (ref "TP07M") (pin "P$1") (pinfunction "1_P$1") (pintype "bidirectional"))
    )
    (net (code "9") (name "EINK_CKV") (class "Default")
      (node (ref "IC2") (pin "6") (pinfunction "GPB5_6") (pintype "bidirectional"))
      (node (ref "J02S") (pin "33") (pinfunction "U1CKV_33") (pintype "bidirectional"))
      (node (ref "R10D") (pin "2") (pinfunction "2_2") (pintype "passive"))
    )
    (net (code "10") (name "EINK_CL") (class "Default")
      (node (ref "IC2") (pin "1") (pinfunction "GPB0_1") (pintype "bidirectional"))
      (node (ref "J02S") (pin "5") (pinfunction "CL_5") (pintype "bidirectional"))
    )
    (net (code "11") (name "EINK_D0") (class "Default")
      (node (ref "IC1") (pin "21") (pinfunction "GPA0_21") (pintype "bidirectional"))
      (node (ref "J02S") (pin "12") (pinfunction "D0_12") (pintype "bidirectional"))
    )
    (net (code "12") (name "EINK_D1") (class "Default")
      (node (ref "IC1") (pin "22") (pinfunction "GPA1_22") (pintype "bidirectional"))
      (node (ref "J02S") (pin "13") (pinfunction "D1_13") (pintype "bidirectional"))
    )
    (net (code "13") (name "EINK_D2") (class "Default")
      (node (ref "IC1") (pin "23") (pinfunction "GPA2_23") (pintype "bidirectional"))
      (node (ref "J02S") (pin "14") (pinfunction "D2_14") (pintype "bidirectional"))
    )
    (net (code "14") (name "EINK_D3") (class "Default")
      (node (ref "IC1") (pin "24") (pinfunction "GPA3_24") (pintype "bidirectional"))
      (node (ref "J02S") (pin "15") (pinfunction "D3_15") (pintype "bidirectional"))
    )
    (net (code "15") (name "EINK_D4") (class "Default")
      (node (ref "IC1") (pin "25") (pinfunction "GPA4_25") (pintype "bidirectional"))
      (node (ref "J02S") (pin "16") (pinfunction "D4_16") (pintype "bidirectional"))
    )
    (net (code "16") (name "EINK_D5") (class "Default")
      (node (ref "IC1") (pin "26") (pinfunction "GPA5_26") (pintype "bidirectional"))
      (node (ref "J02S") (pin "17") (pinfunction "D5_17") (pintype "bidirectional"))
    )
    (net (code "17") (name "EINK_D6") (class "Default")
      (node (ref "IC1") (pin "27") (pinfunction "GPA6_27") (pintype "bidirectional"))
      (node (ref "J02S") (pin "18") (pinfunction "D6_18") (pintype "bidirectional"))
    )
    (net (code "18") (name "EINK_D7") (class "Default")
      (node (ref "IC1") (pin "28") (pinfunction "GPA7_28") (pintype "bidirectional"))
      (node (ref "J02S") (pin "19") (pinfunction "D7_19") (pintype "bidirectional"))
    )
    (net (code "19") (name "EINK_GMODE") (class "Default")
      (node (ref "IC2") (pin "7") (pinfunction "GPB6_7") (pintype "bidirectional"))
      (node (ref "J02S") (pin "28") (pinfunction "GMODE1_28") (pintype "bidirectional"))
      (node (ref "R04D1") (pin "1") (pinfunction "1_1") (pintype "passive"))
    )
    (net (code "20") (name "EINK_LE") (class "Default")
      (node (ref "IC2") (pin "2") (pinfunction "GPB1_2") (pintype "bidirectional"))
      (node (ref "J02S") (pin "6") (pinfunction "LE_6") (pintype "bidirectional"))
    )
    (net (code "21") (name "EINK_OE") (class "Default")
      (node (ref "IC2") (pin "3") (pinfunction "GPB2_3") (pintype "bidirectional"))
      (node (ref "J02S") (pin "7") (pinfunction "OE_7") (pintype "bidirectional"))
    )
    (net (code "22") (name "EINK_RL") (class "Default")
      (node (ref "IC2") (pin "8") (pinfunction "GPB7_8") (pintype "bidirectional"))
      (node (ref "R13D") (pin "1") (pinfunction "1_1") (pintype "passive"))
    )
    (net (code "23") (name "EINK_SHR") (class "Default")
      (node (ref "R12D") (pin "2") (pinfunction "2_2") (pintype "passive"))
    )
    (net (code "24") (name "EINK_SPH") (class "Default")
      (node (ref "IC2") (pin "4") (pinfunction "GPB3_4") (pintype "bidirectional"))
      (node (ref "J02S") (pin "11") (pinfunction "SPH_11") (pintype "bidirectional"))
    )
    (net (code "25") (name "EINK_SPV") (class "Default")
      (node (ref "IC2") (pin "5") (pinfunction "GPB4_5") (pintype "bidirectional"))
      (node (ref "J02S") (pin "32") (pinfunction "U1SPV_32") (pintype "bidirectional"))
      (node (ref "R11D") (pin "2") (pinfunction "2_2") (pintype "passive"))
    )
    (net (code "26") (name "EINK_VBORDER") (class "Default")
      (node (ref "IC2") (pin "21") (pinfunction "GPA0_21") (pintype "bidirectional"))
      (node (ref "J02S") (pin "34") (pinfunction "VBORDER_34") (pintype "bidirectional"))
      (node (ref "R07D") (pin "1") (pinfunction "1_1") (pintype "passive"))
    )
    (net (code "27") (name "EINK_VDD") (class "Default")
      (node (ref "C05D") (pin "1") (pinfunction "1_1") (pintype "passive"))
      (node (ref "J02S") (pin "4") (pinfunction "VDD_4") (pintype "bidirectional"))
      (node (ref "R03D") (pin "1") (pinfunction "1_1") (pintype "passive"))
      (node (ref "R05D") (pin "1") (pinfunction "1_1") (pintype "passive"))
      (node (ref "R08D") (pin "1") (pinfunction "1_1") (pintype "passive"))
      (node (ref "R09D") (pin "1") (pinfunction "1_1") (pintype "passive"))
      (node (ref "TP01M") (pin "P$1") (pinfunction "1_P$1") (pintype "bidirectional"))
    )
    (net (code "28") (name "FB2") (class "Default")
      (node (ref "C10B") (pin "1") (pinfunction "1_1") (pintype "passive"))
      (node (ref "R15B") (pin "1") (pinfunction "1_1") (pintype "passive"))
      (node (ref "R16B") (pin "2") (pinfunction "2_2") (pintype "passive"))
      (node (ref "U03B") (pin "5") (pinfunction "FB2_5") (pintype "bidirectional"))
    )
    (net (code "29") (name "GND") (class "Default")
      (node (ref "C01D") (pin "2") (pinfunction "2_2") (pintype "passive"))
      (node (ref "C02D") (pin "2") (pinfunction "2_2") (pintype "passive"))
      (node (ref "C03D") (pin "2") (pinfunction "2_2") (pintype "passive"))
      (node (ref "C04B") (pin "1") (pinfunction "1_1") (pintype "passive"))
      (node (ref "C04D") (pin "2") (pinfunction "2_2") (pintype "passive"))
      (node (ref "C05B") (pin "1") (pinfunction "1_1") (pintype "passive"))
      (node (ref "C05D") (pin "2") (pinfunction "2_2") (pintype "passive"))
      (node (ref "C06B") (pin "1") (pinfunction "1_1") (pintype "passive"))
      (node (ref "C09B") (pin "1") (pinfunction "1_1") (pintype "passive"))
      (node (ref "C1") (pin "2") (pinfunction "2_2") (pintype "passive"))
      (node (ref "C11B") (pin "1") (pinfunction "1_1") (pintype "passive"))
      (node (ref "C12B") (pin "1") (pinfunction "1_1") (pintype "passive"))
      (node (ref "C13B") (pin "1") (pinfunction "1_1") (pintype "passive"))
      (node (ref "C14B") (pin "1") (pinfunction "1_1") (pintype "passive"))
      (node (ref "C15B") (pin "1") (pinfunction "1_1") (pintype "passive"))
      (node (ref "C16B") (pin "1") (pinfunction "1_1") (pintype "passive"))
      (node (ref "C17B") (pin "1") (pinfunction "1_1") (pintype "passive"))
      (node (ref "CFG") (pin "2") (pinfunction "2_2") (pintype "passive"))
      (node (ref "D03B") (pin "C") (pinfunction "C_C") (pintype "passive"))
      (node (ref "IC1") (pin "10") (pinfunction "VSS_10") (pintype "power_in"))
      (node (ref "IC2") (pin "10") (pinfunction "VSS_10") (pintype "power_in"))
      (node (ref "J02S") (pin "3") (pinfunction "VSS_3") (pintype "bidirectional"))
      (node (ref "K1") (pin "14") (pinfunction "14_14") (pintype "passive"))
      (node (ref "K1") (pin "20") (pinfunction "20_20") (pintype "passive"))
      (node (ref "K1") (pin "25") (pinfunction "25_25") (pintype "passive"))
      (node (ref "K1") (pin "30") (pinfunction "30_30") (pintype "passive"))
      (node (ref "K1") (pin "34") (pinfunction "34_34") (pintype "passive"))
      (node (ref "K1") (pin "39") (pinfunction "39_39") (pintype "passive"))
      (node (ref "K1") (pin "6") (pinfunction "6_6") (pintype "passive"))
      (node (ref "K1") (pin "9") (pinfunction "9_9") (pintype "passive"))
      (node (ref "R02D") (pin "2") (pinfunction "2_2") (pintype "passive"))
      (node (ref "R06D") (pin "1") (pinfunction "1_1") (pintype "passive"))
      (node (ref "R07D") (pin "2") (pinfunction "2_2") (pintype "passive"))
      (node (ref "R14B") (pin "1") (pinfunction "1_1") (pintype "passive"))
      (node (ref "R16B") (pin "1") (pinfunction "1_1") (pintype "passive"))
      (node (ref "R18B") (pin "1") (pinfunction "A_1") (pintype "passive"))
      (node (ref "R23B") (pin "2") (pinfunction "2_2") (pintype "passive"))
      (node (ref "R24B") (pin "2") (pinfunction "2_2") (pintype "passive"))
      (node (ref "R26B") (pin "1") (pinfunction "1_1") (pintype "passive"))
      (node (ref "R5") (pin "1") (pinfunction "1_1") (pintype "passive"))
      (node (ref "R6") (pin "1") (pinfunction "1_1") (pintype "passive"))
      (node (ref "R7") (pin "1") (pinfunction "1_1") (pintype "passive"))
      (node (ref "R8") (pin "1") (pinfunction "1_1") (pintype "passive"))
      (node (ref "R9") (pin "1") (pinfunction "1_1") (pintype "passive"))
      (node (ref "U02B") (pin "2") (pinfunction "GND_2") (pintype "bidirectional"))
      (node (ref "U03B") (pin "3") (pinfunction "GND_3") (pintype "bidirectional"))
      (node (ref "U03B") (pin "7") (pinfunction "PGND_7") (pintype "bidirectional"))
      (node (ref "U03B") (pin "9") (pinfunction "PGND_9") (pintype "bidirectional"))
      (node (ref "U04B") (pin "5") (pinfunction "GND_5") (pintype "bidirectional"))
      (node (ref "U05B") (pin "2") (pinfunction "GND_2") (pintype "bidirectional"))
      (node (ref "U05B") (pin "3") (pinfunction "GND_3") (pintype "bidirectional"))
      (node (ref "U05B") (pin "6") (pinfunction "GND_6") (pintype "bidirectional"))
      (node (ref "U05B") (pin "7") (pinfunction "GND_7") (pintype "bidirectional"))
      (node (ref "U1") (pin "1") (pinfunction "A0_1") (pintype "input"))
      (node (ref "U1") (pin "2") (pinfunction "A1_2") (pintype "input"))
      (node (ref "U1") (pin "3") (pinfunction "A2_3") (pintype "input"))
      (node (ref "U1") (pin "4") (pinfunction "GND_4") (pintype "power_in"))
    )
    (net (code "30") (name "GND1") (class "Default")
      (node (ref "IC3") (pin "11") (pinfunction "GND1_11") (pintype "power_in"))
    )
    (net (code "31") (name "GND2") (class "Default")
      (node (ref "IC3") (pin "12") (pinfunction "GND2_12") (pintype "power_in"))
    )
    (net (code "32") (name "GND3") (class "Default")
      (node (ref "IC3") (pin "13") (pinfunction "GND3_13") (pintype "power_in"))
    )
    (net (code "33") (name "MCU_SCL") (class "Default")
      (node (ref "TP18M") (pin "P$1") (pinfunction "TP_P$1") (pintype "bidirectional"))
    )
    (net (code "34") (name "MCU_SDA") (class "Default")
      (node (ref "TP17M") (pin "P$1") (pinfunction "TP_P$1") (pintype "bidirectional"))
    )
    (net (code "35") (name "N$17") (class "Default")
      (node (ref "K1") (pin "29") (pinfunction "29_29") (pintype "passive"))
    )
    (net (code "36") (name "N$18") (class "Default")
      (node (ref "K1") (pin "31") (pinfunction "31_31") (pintype "passive"))
    )
    (net (code "37") (name "N$19") (class "Default")
      (node (ref "K1") (pin "33") (pinfunction "33_33") (pintype "passive"))
    )
    (net (code "38") (name "N$20") (class "Default")
      (node (ref "K1") (pin "35") (pinfunction "35_35") (pintype "passive"))
    )
    (net (code "39") (name "N$22") (class "Default")
      (node (ref "K1") (pin "37") (pinfunction "37_37") (pintype "passive"))
    )
    (net (code "40") (name "NEG_EN") (class "Default")
      (node (ref "IC2") (pin "24") (pinfunction "GPA3_24") (pintype "bidirectional"))
      (node (ref "R23B") (pin "1") (pinfunction "1_1") (pintype "passive"))
      (node (ref "U03B") (pin "2") (pinfunction "~{SHDN1}_2") (pintype "bidirectional"))
    )
    (net (code "41") (name "NFB1") (class "Default")
      (node (ref "C08B") (pin "1") (pinfunction "1_1") (pintype "passive"))
      (node (ref "R13B") (pin "1") (pinfunction "1_1") (pintype "passive"))
      (node (ref "R14B") (pin "2") (pinfunction "2_2") (pintype "passive"))
      (node (ref "U03B") (pin "1") (pinfunction "NFB1_1") (pintype "bidirectional"))
    )
    (net (code "42") (name "Net-(C07B-Pad2)") (class "Default")
      (node (ref "C07B") (pin "2") (pinfunction "2_2") (pintype "passive"))
      (node (ref "D03B") (pin "A") (pinfunction "A_A") (pintype "passive"))
      (node (ref "D04B") (pin "C") (pinfunction "C_C") (pintype "passive"))
    )
    (net (code "43") (name "Net-(IC1-A0)") (class "Default")
      (node (ref "IC1") (pin "15") (pinfunction "A0_15") (pintype "input"))
      (node (ref "R6") (pin "2") (pinfunction "2_2") (pintype "passive"))
      (node (ref "SJ3") (pin "2") (pinfunction "2_2") (pintype "passive"))
    )
    (net (code "44") (name "Net-(IC1-A1)") (class "Default")
      (node (ref "IC1") (pin "16") (pinfunction "A1_16") (pintype "input"))
      (node (ref "R5") (pin "2") (pinfunction "2_2") (pintype "passive"))
      (node (ref "SJ4") (pin "2") (pinfunction "2_2") (pintype "passive"))
    )
    (net (code "45") (name "Net-(IC1-A2)") (class "Default")
      (node (ref "IC1") (pin "17") (pinfunction "A2_17") (pintype "input"))
      (node (ref "R4") (pin "2") (pinfunction "2_2") (pintype "passive"))
    )
    (net (code "46") (name "Net-(IC2-A0)") (class "Default")
      (node (ref "IC2") (pin "15") (pinfunction "A0_15") (pintype "input"))
      (node (ref "R9") (pin "2") (pinfunction "2_2") (pintype "passive"))
      (node (ref "SJ1") (pin "2") (pinfunction "2_2") (pintype "passive"))
    )
    (net (code "47") (name "Net-(IC2-A1)") (class "Default")
      (node (ref "IC2") (pin "16") (pinfunction "A1_16") (pintype "input"))
      (node (ref "R8") (pin "2") (pinfunction "2_2") (pintype "passive"))
      (node (ref "SJ2") (pin "2") (pinfunction "2_2") (pintype "passive"))
    )
    (net (code "48") (name "Net-(IC2-A2)") (class "Default")
      (node (ref "IC2") (pin "17") (pinfunction "A2_17") (pintype "input"))
      (node (ref "R7") (pin "2") (pinfunction "2_2") (pintype "passive"))
    )
    (net (code "49") (name "Net-(J02S-CE1)") (class "Default")
      (node (ref "J02S") (pin "9") (pinfunction "CE1_9") (pintype "bidirectional"))
      (node (ref "R02D") (pin "1") (pinfunction "1_1") (pintype "passive"))
    )
    (net (code "50") (name "Net-(J02S-CE2)") (class "Default")
      (node (ref "J02S") (pin "10") (pinfunction "CE2_10") (pintype "bidirectional"))
      (node (ref "R03D") (pin "2") (pinfunction "2_2") (pintype "passive"))
    )
    (net (code "51") (name "Net-(J02S-GMODE2)") (class "Default")
      (node (ref "J02S") (pin "27") (pinfunction "GMODE2_27") (pintype "bidirectional"))
      (node (ref "R04D1") (pin "2") (pinfunction "2_2") (pintype "passive"))
    )
    (net (code "52") (name "Net-(J02S-NC-20)") (class "Default")
      (node (ref "J02S") (pin "20") (pinfunction "NC-20_20") (pintype "bidirectional"))
      (node (ref "U$1") (pin "P$1") (pinfunction "TP_P$1") (pintype "bidirectional"))
    )
    (net (code "53") (name "Net-(J02S-NC-26)") (class "Default")
      (node (ref "J02S") (pin "26") (pinfunction "NC-26_26") (pintype "bidirectional"))
      (node (ref "U$8") (pin "P$1") (pinfunction "TP_P$1") (pintype "bidirectional"))
    )
    (net (code "54") (name "Net-(J02S-NC-39)") (class "Default")
      (node (ref "J02S") (pin "39") (pinfunction "NC-39_39") (pintype "bidirectional"))
      (node (ref "U$9") (pin "P$1") (pinfunction "TP_P$1") (pintype "bidirectional"))
    )
    (net (code "55") (name "Net-(J02S-RL)") (class "Default")
      (node (ref "J02S") (pin "29") (pinfunction "RL_29") (pintype "bidirectional"))
      (node (ref "R13D") (pin "2") (pinfunction "2_2") (pintype "passive"))
    )
    (net (code "56") (name "Net-(J02S-SHR)") (class "Default")
      (node (ref "J02S") (pin "8") (pinfunction "SHR_8") (pintype "bidirectional"))
      (node (ref "R12D") (pin "1") (pinfunction "1_1") (pintype "passive"))
    )
    (net (code "57") (name "Net-(J02S-U1CE1)") (class "Default")
      (node (ref "J02S") (pin "31") (pinfunction "U1CE1_31") (pintype "bidirectional"))
      (node (ref "R06D") (pin "2") (pinfunction "2_2") (pintype "passive"))
    )
    (net (code "58") (name "Net-(J02S-U1CE2)") (class "Default")
      (node (ref "J02S") (pin "30") (pinfunction "U1CE2_30") (pintype "bidirectional"))
      (node (ref "R05D") (pin "2") (pinfunction "2_2") (pintype "passive"))
    )
    (net (code "59") (name "Net-(J02S-U2CE1)") (class "Default")
      (node (ref "J02S") (pin "36") (pinfunction "U2CE1_36") (pintype "bidirectional"))
      (node (ref "R09D") (pin "2") (pinfunction "2_2") (pintype "passive"))
    )
    (net (code "60") (name "Net-(J02S-U2CE2)") (class "Default")
      (node (ref "J02S") (pin "35") (pinfunction "U2CE2_35") (pintype "bidirectional"))
      (node (ref "R08D") (pin "2") (pinfunction "2_2") (pintype "passive"))
    )
    (net (code "61") (name "Net-(J02S-U2CKV)") (class "Default")
      (node (ref "J02S") (pin "38") (pinfunction "U2CKV_38") (pintype "bidirectional"))
      (node (ref "R10D") (pin "1") (pinfunction "1_1") (pintype "passive"))
    )
    (net (code "62") (name "Net-(J02S-U2SPV)") (class "Default")
      (node (ref "J02S") (pin "37") (pinfunction "U2SPV_37") (pintype "bidirectional"))
      (node (ref "R11D") (pin "1") (pinfunction "1_1") (pintype "passive"))
    )
    (net (code "63") (name "Net-(Q02B-D)") (class "Default")
      (node (ref "L03B") (pin "P$1") (pinfunction "P$1_P$1") (pintype "bidirectional"))
      (node (ref "Q02B") (pin "3") (pinfunction "D_3") (pintype "passive"))
    )
    (net (code "64") (name "Net-(R18B-E)") (class "Default")
      (node (ref "R17B") (pin "1") (pinfunction "1_1") (pintype "passive"))
      (node (ref "R18B") (pin "3") (pinfunction "E_3") (pintype "passive"))
      (node (ref "R26B") (pin "2") (pinfunction "2_2") (pintype "passive"))
    )
    (net (code "65") (name "Net-(R18B-S)") (class "Default")
      (node (ref "R18B") (pin "2") (pinfunction "S_2") (pintype "passive"))
      (node (ref "U06B") (pin "5") (pinfunction "+IN2_5") (pintype "input"))
    )
    (net (code "66") (name "Net-(TP01B-TP)") (class "Default")
      (node (ref "R11B") (pin "1") (pinfunction "1_1") (pintype "passive"))
      (node (ref "TP01B") (pin "P$1") (pinfunction "TP_P$1") (pintype "bidirectional"))
      (node (ref "U02B") (pin "1") (pinfunction "EN_1") (pintype "bidirectional"))
    )
    (net (code "67") (name "Net-(U1-SCL)") (class "Default")
      (node (ref "K1") (pin "28") (pinfunction "28_28") (pintype "passive"))
      (node (ref "R1") (pin "1") (pinfunction "1_1") (pintype "passive"))
      (node (ref "U1") (pin "6") (pinfunction "SCL_6") (pintype "input"))
    )
    (net (code "68") (name "Net-(U1-SDA)") (class "Default")
      (node (ref "K1") (pin "27") (pinfunction "27_27") (pintype "passive"))
      (node (ref "R2") (pin "1") (pinfunction "1_1") (pintype "passive"))
      (node (ref "U1") (pin "5") (pinfunction "SDA_5") (pintype "bidirectional"))
    )
    (net (code "69") (name "Net-(U1-WP)") (class "Default")
      (node (ref "CFG") (pin "1") (pinfunction "1_1") (pintype "passive"))
      (node (ref "R3") (pin "1") (pinfunction "1_1") (pintype "passive"))
      (node (ref "U1") (pin "7") (pinfunction "WP_7") (pintype "input"))
    )
    (net (code "70") (name "Net-(U02B-LX)") (class "Default")
      (node (ref "L01B") (pin "1") (pinfunction "1_1") (pintype "passive"))
      (node (ref "U02B") (pin "3") (pinfunction "LX_3") (pintype "bidirectional"))
    )
    (net (code "71") (name "Net-(U03B-SW1)") (class "Default")
      (node (ref "C07B") (pin "1") (pinfunction "1_1") (pintype "passive"))
      (node (ref "L02B") (pin "P$2") (pinfunction "P$2_P$2") (pintype "bidirectional"))
      (node (ref "U03B") (pin "10") (pinfunction "SW1_10") (pintype "bidirectional"))
    )
    (net (code "72") (name "Net-(U03B-SW2)") (class "Default")
      (node (ref "D05B") (pin "A") (pinfunction "A_A") (pintype "passive"))
      (node (ref "L03B") (pin "P$2") (pinfunction "P$2_P$2") (pintype "bidirectional"))
      (node (ref "U03B") (pin "6") (pinfunction "SW2_6") (pintype "bidirectional"))
    )
    (net (code "73") (name "POS_CTRL") (class "Default")
      (node (ref "IC2") (pin "25") (pinfunction "GPA4_25") (pintype "bidirectional"))
      (node (ref "Q02B") (pin "1") (pinfunction "G_1") (pintype "passive"))
      (node (ref "R25B") (pin "1") (pinfunction "1_1") (pintype "passive"))
      (node (ref "TP2") (pin "P$1") (pinfunction "1_P$1") (pintype "bidirectional"))
    )
    (net (code "74") (name "POS_EN") (class "Default")
      (node (ref "IC2") (pin "23") (pinfunction "GPA2_23") (pintype "bidirectional"))
      (node (ref "R24B") (pin "1") (pinfunction "1_1") (pintype "passive"))
      (node (ref "U03B") (pin "4") (pinfunction "~{SHDN2}_4") (pintype "bidirectional"))
    )
    (net (code "75") (name "SD_CS") (class "Default")
      (node (ref "TP05M") (pin "P$1") (pinfunction "1_P$1") (pintype "bidirectional"))
    )
    (net (code "76") (name "SMPS_CTRL") (class "Default")
      (node (ref "IC2") (pin "22") (pinfunction "GPA1_22") (pintype "bidirectional"))
      (node (ref "Q01B") (pin "1") (pinfunction "G_1") (pintype "passive"))
      (node (ref "R12B") (pin "1") (pinfunction "1_1") (pintype "passive"))
      (node (ref "TP1") (pin "P$1") (pinfunction "1_P$1") (pintype "bidirectional"))
    )
    (net (code "77") (name "SPI_CE0_N") (class "Default")
      (node (ref "K1") (pin "24") (pinfunction "24_24") (pintype "passive"))
    )
    (net (code "78") (name "SPI_CE1_N") (class "Default")
      (node (ref "K1") (pin "26") (pinfunction "26_26") (pintype "passive"))
    )
    (net (code "79") (name "SPI_CLK") (class "Default")
      (node (ref "IC1") (pin "12") (pinfunction "SCK_12") (pintype "input"))
      (node (ref "IC2") (pin "12") (pinfunction "SCK_12") (pintype "input"))
      (node (ref "K1") (pin "23") (pinfunction "23_23") (pintype "passive"))
    )
    (net (code "80") (name "SPI_MISO") (class "Default")
      (node (ref "IC1") (pin "14") (pinfunction "SO_14") (pintype "output"))
      (node (ref "IC2") (pin "14") (pinfunction "SO_14") (pintype "output"))
      (node (ref "K1") (pin "21") (pinfunction "21_21") (pintype "passive"))
      (node (ref "TP03M") (pin "P$1") (pinfunction "1_P$1") (pintype "bidirectional"))
    )
    (net (code "81") (name "SPI_MOSI") (class "Default")
      (node (ref "IC1") (pin "13") (pinfunction "SI_13") (pintype "input"))
      (node (ref "IC2") (pin "13") (pinfunction "SI_13") (pintype "input"))
      (node (ref "K1") (pin "19") (pinfunction "19_19") (pintype "passive"))
      (node (ref "TP02M") (pin "P$1") (pinfunction "1_P$1") (pintype "bidirectional"))
    )
    (net (code "82") (name "SPI_SCK") (class "Default")
      (node (ref "TP04M") (pin "P$1") (pinfunction "1_P$1") (pintype "bidirectional"))
    )
    (net (code "83") (name "USB_DISC") (class "Default")
      (node (ref "TP06M") (pin "P$1") (pinfunction "1_P$1") (pintype "bidirectional"))
    )
    (net (code "84") (name "VCCA") (class "Default")
      (node (ref "IC3") (pin "1") (pinfunction "VCCA_1") (pintype "power_in"))
    )
    (net (code "85") (name "VCCB1") (class "Default")
      (node (ref "IC3") (pin "24") (pinfunction "VCCB1_24") (pintype "power_in"))
    )
    (net (code "86") (name "VCCB2") (class "Default")
      (node (ref "IC3") (pin "23") (pinfunction "VCCB2_23") (pintype "power_in"))
    )
    (net (code "87") (name "VCOM") (class "Default")
      (node (ref "C17B") (pin "2") (pinfunction "2_2") (pintype "passive"))
      (node (ref "J02S") (pin "22") (pinfunction "VCOM_22") (pintype "bidirectional"))
      (node (ref "J11B") (pin "1") (pinfunction "1_1") (pintype "passive"))
      (node (ref "U06B") (pin "6") (pinfunction "-IN2_6") (pintype "input"))
      (node (ref "U06B") (pin "7") (pinfunction "OUT2_7") (pintype "output"))
    )
    (net (code "88") (name "VIN") (class "Default")
      (node (ref "C09B") (pin "2") (pinfunction "2_2") (pintype "passive"))
      (node (ref "J06B") (pin "1") (pinfunction "1_1") (pintype "passive"))
      (node (ref "L02B") (pin "P$1") (pinfunction "P$1_P$1") (pintype "bidirectional"))
      (node (ref "Q01B") (pin "3") (pinfunction "D_3") (pintype "passive"))
      (node (ref "Q02B") (pin "2") (pinfunction "S_2") (pintype "passive"))
      (node (ref "R25B") (pin "2") (pinfunction "2_2") (pintype "passive"))
      (node (ref "U03B") (pin "8") (pinfunction "VIN_8") (pintype "bidirectional"))
    )
    (net (code "89") (name "unconnected-(IC1-GPB0-Pad1)") (class "Default")
      (node (ref "IC1") (pin "1") (pinfunction "GPB0_1") (pintype "bidirectional"))
    )
    (net (code "90") (name "unconnected-(IC1-GPB1-Pad2)") (class "Default")
      (node (ref "IC1") (pin "2") (pinfunction "GPB1_2") (pintype "bidirectional"))
    )
    (net (code "91") (name "unconnected-(IC1-GPB2-Pad3)") (class "Default")
      (node (ref "IC1") (pin "3") (pinfunction "GPB2_3") (pintype "bidirectional"))
    )
    (net (code "92") (name "unconnected-(IC1-GPB3-Pad4)") (class "Default")
      (node (ref "IC1") (pin "4") (pinfunction "GPB3_4") (pintype "bidirectional"))
    )
    (net (code "93") (name "unconnected-(IC1-GPB4-Pad5)") (class "Default")
      (node (ref "IC1") (pin "5") (pinfunction "GPB4_5") (pintype "bidirectional"))
    )
    (net (code "94") (name "unconnected-(IC1-GPB5-Pad6)") (class "Default")
      (node (ref "IC1") (pin "6") (pinfunction "GPB5_6") (pintype "bidirectional"))
    )
    (net (code "95") (name "unconnected-(IC1-GPB6-Pad7)") (class "Default")
      (node (ref "IC1") (pin "7") (pinfunction "GPB6_7") (pintype "bidirectional"))
    )
    (net (code "96") (name "unconnected-(IC1-GPB7-Pad8)") (class "Default")
      (node (ref "IC1") (pin "8") (pinfunction "GPB7_8") (pintype "bidirectional"))
    )
    (net (code "97") (name "unconnected-(IC1-INTA-Pad20)") (class "Default")
      (node (ref "IC1") (pin "20") (pinfunction "INTA_20") (pintype "output"))
    )
    (net (code "98") (name "unconnected-(IC1-INTB-Pad19)") (class "Default")
      (node (ref "IC1") (pin "19") (pinfunction "INTB_19") (pintype "output"))
    )
    (net (code "99") (name "unconnected-(IC1-~{CS}-Pad11)") (class "Default")
      (node (ref "IC1") (pin "11") (pinfunction "~{CS}_11") (pintype "input"))
    )
    (net (code "100") (name "unconnected-(IC1-~{RESET}-Pad18)") (class "Default")
      (node (ref "IC1") (pin "18") (pinfunction "~{RESET}_18") (pintype "input"))
    )
    (net (code "101") (name "unconnected-(IC2-GPA5-Pad26)") (class "Default")
      (node (ref "IC2") (pin "26") (pinfunction "GPA5_26") (pintype "bidirectional"))
    )
    (net (code "102") (name "unconnected-(IC2-GPA6-Pad27)") (class "Default")
      (node (ref "IC2") (pin "27") (pinfunction "GPA6_27") (pintype "bidirectional"))
    )
    (net (code "103") (name "unconnected-(IC2-GPA7-Pad28)") (class "Default")
      (node (ref "IC2") (pin "28") (pinfunction "GPA7_28") (pintype "bidirectional"))
    )
    (net (code "104") (name "unconnected-(IC2-INTA-Pad20)") (class "Default")
      (node (ref "IC2") (pin "20") (pinfunction "INTA_20") (pintype "output"))
    )
    (net (code "105") (name "unconnected-(IC2-INTB-Pad19)") (class "Default")
      (node (ref "IC2") (pin "19") (pinfunction "INTB_19") (pintype "output"))
    )
    (net (code "106") (name "unconnected-(IC2-~{CS}-Pad11)") (class "Default")
      (node (ref "IC2") (pin "11") (pinfunction "~{CS}_11") (pintype "input"))
    )
    (net (code "107") (name "unconnected-(IC2-~{RESET}-Pad18)") (class "Default")
      (node (ref "IC2") (pin "18") (pinfunction "~{RESET}_18") (pintype "input"))
    )
    (net (code "108") (name "unconnected-(IC3-A1-Pad3)") (class "Default")
      (node (ref "IC3") (pin "3") (pinfunction "A1_3") (pintype "bidirectional"))
    )
    (net (code "109") (name "unconnected-(IC3-A2-Pad4)") (class "Default")
      (node (ref "IC3") (pin "4") (pinfunction "A2_4") (pintype "bidirectional"))
    )
    (net (code "110") (name "unconnected-(IC3-A3-Pad5)") (class "Default")
      (node (ref "IC3") (pin "5") (pinfunction "A3_5") (pintype "bidirectional"))
    )
    (net (code "111") (name "unconnected-(IC3-A4-Pad6)") (class "Default")
      (node (ref "IC3") (pin "6") (pinfunction "A4_6") (pintype "bidirectional"))
    )
    (net (code "112") (name "unconnected-(IC3-A5-Pad7)") (class "Default")
      (node (ref "IC3") (pin "7") (pinfunction "A5_7") (pintype "bidirectional"))
    )
    (net (code "113") (name "unconnected-(IC3-A6-Pad8)") (class "Default")
      (node (ref "IC3") (pin "8") (pinfunction "A6_8") (pintype "bidirectional"))
    )
    (net (code "114") (name "unconnected-(IC3-A7-Pad9)") (class "Default")
      (node (ref "IC3") (pin "9") (pinfunction "A7_9") (pintype "bidirectional"))
    )
    (net (code "115") (name "unconnected-(IC3-A8-Pad10)") (class "Default")
      (node (ref "IC3") (pin "10") (pinfunction "A8_10") (pintype "bidirectional"))
    )
    (net (code "116") (name "unconnected-(IC3-B1-Pad21)") (class "Default")
      (node (ref "IC3") (pin "21") (pinfunction "B1_21") (pintype "bidirectional"))
    )
    (net (code "117") (name "unconnected-(IC3-B2-Pad20)") (class "Default")
      (node (ref "IC3") (pin "20") (pinfunction "B2_20") (pintype "bidirectional"))
    )
    (net (code "118") (name "unconnected-(IC3-B3-Pad19)") (class "Default")
      (node (ref "IC3") (pin "19") (pinfunction "B3_19") (pintype "bidirectional"))
    )
    (net (code "119") (name "unconnected-(IC3-B4-Pad18)") (class "Default")
      (node (ref "IC3") (pin "18") (pinfunction "B4_18") (pintype "bidirectional"))
    )
    (net (code "120") (name "unconnected-(IC3-B5-Pad17)") (class "Default")
      (node (ref "IC3") (pin "17") (pinfunction "B5_17") (pintype "bidirectional"))
    )
    (net (code "121") (name "unconnected-(IC3-B6-Pad16)") (class "Default")
      (node (ref "IC3") (pin "16") (pinfunction "B6_16") (pintype "bidirectional"))
    )
    (net (code "122") (name "unconnected-(IC3-B7-Pad15)") (class "Default")
      (node (ref "IC3") (pin "15") (pinfunction "B7_15") (pintype "bidirectional"))
    )
    (net (code "123") (name "unconnected-(IC3-B8-Pad14)") (class "Default")
      (node (ref "IC3") (pin "14") (pinfunction "B8_14") (pintype "bidirectional"))
    )
    (net (code "124") (name "unconnected-(IC3-DIR-Pad2)") (class "Default")
      (node (ref "IC3") (pin "2") (pinfunction "DIR_2") (pintype "input"))
    )
    (net (code "125") (name "unconnected-(IC3-OE-Pad22)") (class "Default")
      (node (ref "IC3") (pin "22") (pinfunction "OE_22") (pintype "input"))
    )
    (net (code "126") (name "unconnected-(J02S-NC-21-Pad21)") (class "Default")
      (node (ref "J02S") (pin "21") (pinfunction "NC-21_21") (pintype "bidirectional"))
    )
    (net (code "127") (name "unconnected-(J02S-NC-25-Pad25)") (class "Default")
      (node (ref "J02S") (pin "25") (pinfunction "NC-25_25") (pintype "bidirectional"))
    )
    (net (code "128") (name "unconnected-(K1-Pad3)") (class "Default")
      (node (ref "K1") (pin "3") (pinfunction "3_3") (pintype "passive"))
    )
    (net (code "129") (name "unconnected-(K1-Pad5)") (class "Default")
      (node (ref "K1") (pin "5") (pinfunction "5_5") (pintype "passive"))
    )
    (net (code "130") (name "unconnected-(K1-Pad7)") (class "Default")
      (node (ref "K1") (pin "7") (pinfunction "7_7") (pintype "passive"))
    )
    (net (code "131") (name "unconnected-(K1-Pad8)") (class "Default")
      (node (ref "K1") (pin "8") (pinfunction "8_8") (pintype "passive"))
    )
    (net (code "132") (name "unconnected-(K1-Pad10)") (class "Default")
      (node (ref "K1") (pin "10") (pinfunction "10_10") (pintype "passive"))
    )
    (net (code "133") (name "unconnected-(K1-Pad11)") (class "Default")
      (node (ref "K1") (pin "11") (pinfunction "11_11") (pintype "passive"))
    )
    (net (code "134") (name "unconnected-(K1-Pad12)") (class "Default")
      (node (ref "K1") (pin "12") (pinfunction "12_12") (pintype "passive"))
    )
    (net (code "135") (name "unconnected-(K1-Pad13)") (class "Default")
      (node (ref "K1") (pin "13") (pinfunction "13_13") (pintype "passive"))
    )
    (net (code "136") (name "unconnected-(K1-Pad15)") (class "Default")
      (node (ref "K1") (pin "15") (pinfunction "15_15") (pintype "passive"))
    )
    (net (code "137") (name "unconnected-(K1-Pad16)") (class "Default")
      (node (ref "K1") (pin "16") (pinfunction "16_16") (pintype "passive"))
    )
    (net (code "138") (name "unconnected-(K1-Pad18)") (class "Default")
      (node (ref "K1") (pin "18") (pinfunction "18_18") (pintype "passive"))
    )
    (net (code "139") (name "unconnected-(K1-Pad22)") (class "Default")
      (node (ref "K1") (pin "22") (pinfunction "22_22") (pintype "passive"))
    )
    (net (code "140") (name "unconnected-(K1-Pad32)") (class "Default")
      (node (ref "K1") (pin "32") (pinfunction "32_32") (pintype "passive"))
    )
    (net (code "141") (name "unconnected-(K1-Pad36)") (class "Default")
      (node (ref "K1") (pin "36") (pinfunction "36_36") (pintype "passive"))
    )
    (net (code "142") (name "unconnected-(K1-Pad38)") (class "Default")
      (node (ref "K1") (pin "38") (pinfunction "38_38") (pintype "passive"))
    )
    (net (code "143") (name "unconnected-(K1-Pad40)") (class "Default")
      (node (ref "K1") (pin "40") (pinfunction "40_40") (pintype "passive"))
    )
    (net (code "144") (name "unconnected-(SJ1-Pad1)") (class "Default")
      (node (ref "SJ1") (pin "1") (pinfunction "1_1") (pintype "passive"))
    )
    (net (code "145") (name "unconnected-(SJ2-Pad1)") (class "Default")
      (node (ref "SJ2") (pin "1") (pinfunction "1_1") (pintype "passive"))
    )
    (net (code "146") (name "unconnected-(SJ3-Pad1)") (class "Default")
      (node (ref "SJ3") (pin "1") (pinfunction "1_1") (pintype "passive"))
    )
    (net (code "147") (name "unconnected-(SJ4-Pad1)") (class "Default")
      (node (ref "SJ4") (pin "1") (pinfunction "1_1") (pintype "passive"))
    )
    (net (code "148") (name "unconnected-(U04B-NC-Pad4)") (class "Default")
      (node (ref "U04B") (pin "4") (pinfunction "NC_4") (pintype "bidirectional"))
    )
    (net (code "149") (name "unconnected-(U04B-NC-Pad8)") (class "Default")
      (node (ref "U04B") (pin "8") (pinfunction "NC_8") (pintype "bidirectional"))
    )
    (net (code "150") (name "unconnected-(U05B-NC-Pad4)") (class "Default")
      (node (ref "U05B") (pin "4") (pinfunction "NC_4") (pintype "bidirectional"))
    )
    (net (code "151") (name "unconnected-(U05B-NC-Pad5)") (class "Default")
      (node (ref "U05B") (pin "5") (pinfunction "NC_5") (pintype "bidirectional"))
    )
    (net (code "152") (name "unconnected-(U06B-+IN1-Pad3)") (class "Default")
      (node (ref "U06B") (pin "3") (pinfunction "+IN1_3") (pintype "input"))
    )
    (net (code "153") (name "unconnected-(U06B--IN1-Pad2)") (class "Default")
      (node (ref "U06B") (pin "2") (pinfunction "-IN1_2") (pintype "input"))
    )
    (net (code "154") (name "unconnected-(U06B-OUT1-Pad1)") (class "Default")
      (node (ref "U06B") (pin "1") (pinfunction "OUT1_1") (pintype "output"))
    )
  )
)
